# RX08b19.net
KiCad netlist of a schematic drawn in EAGLE
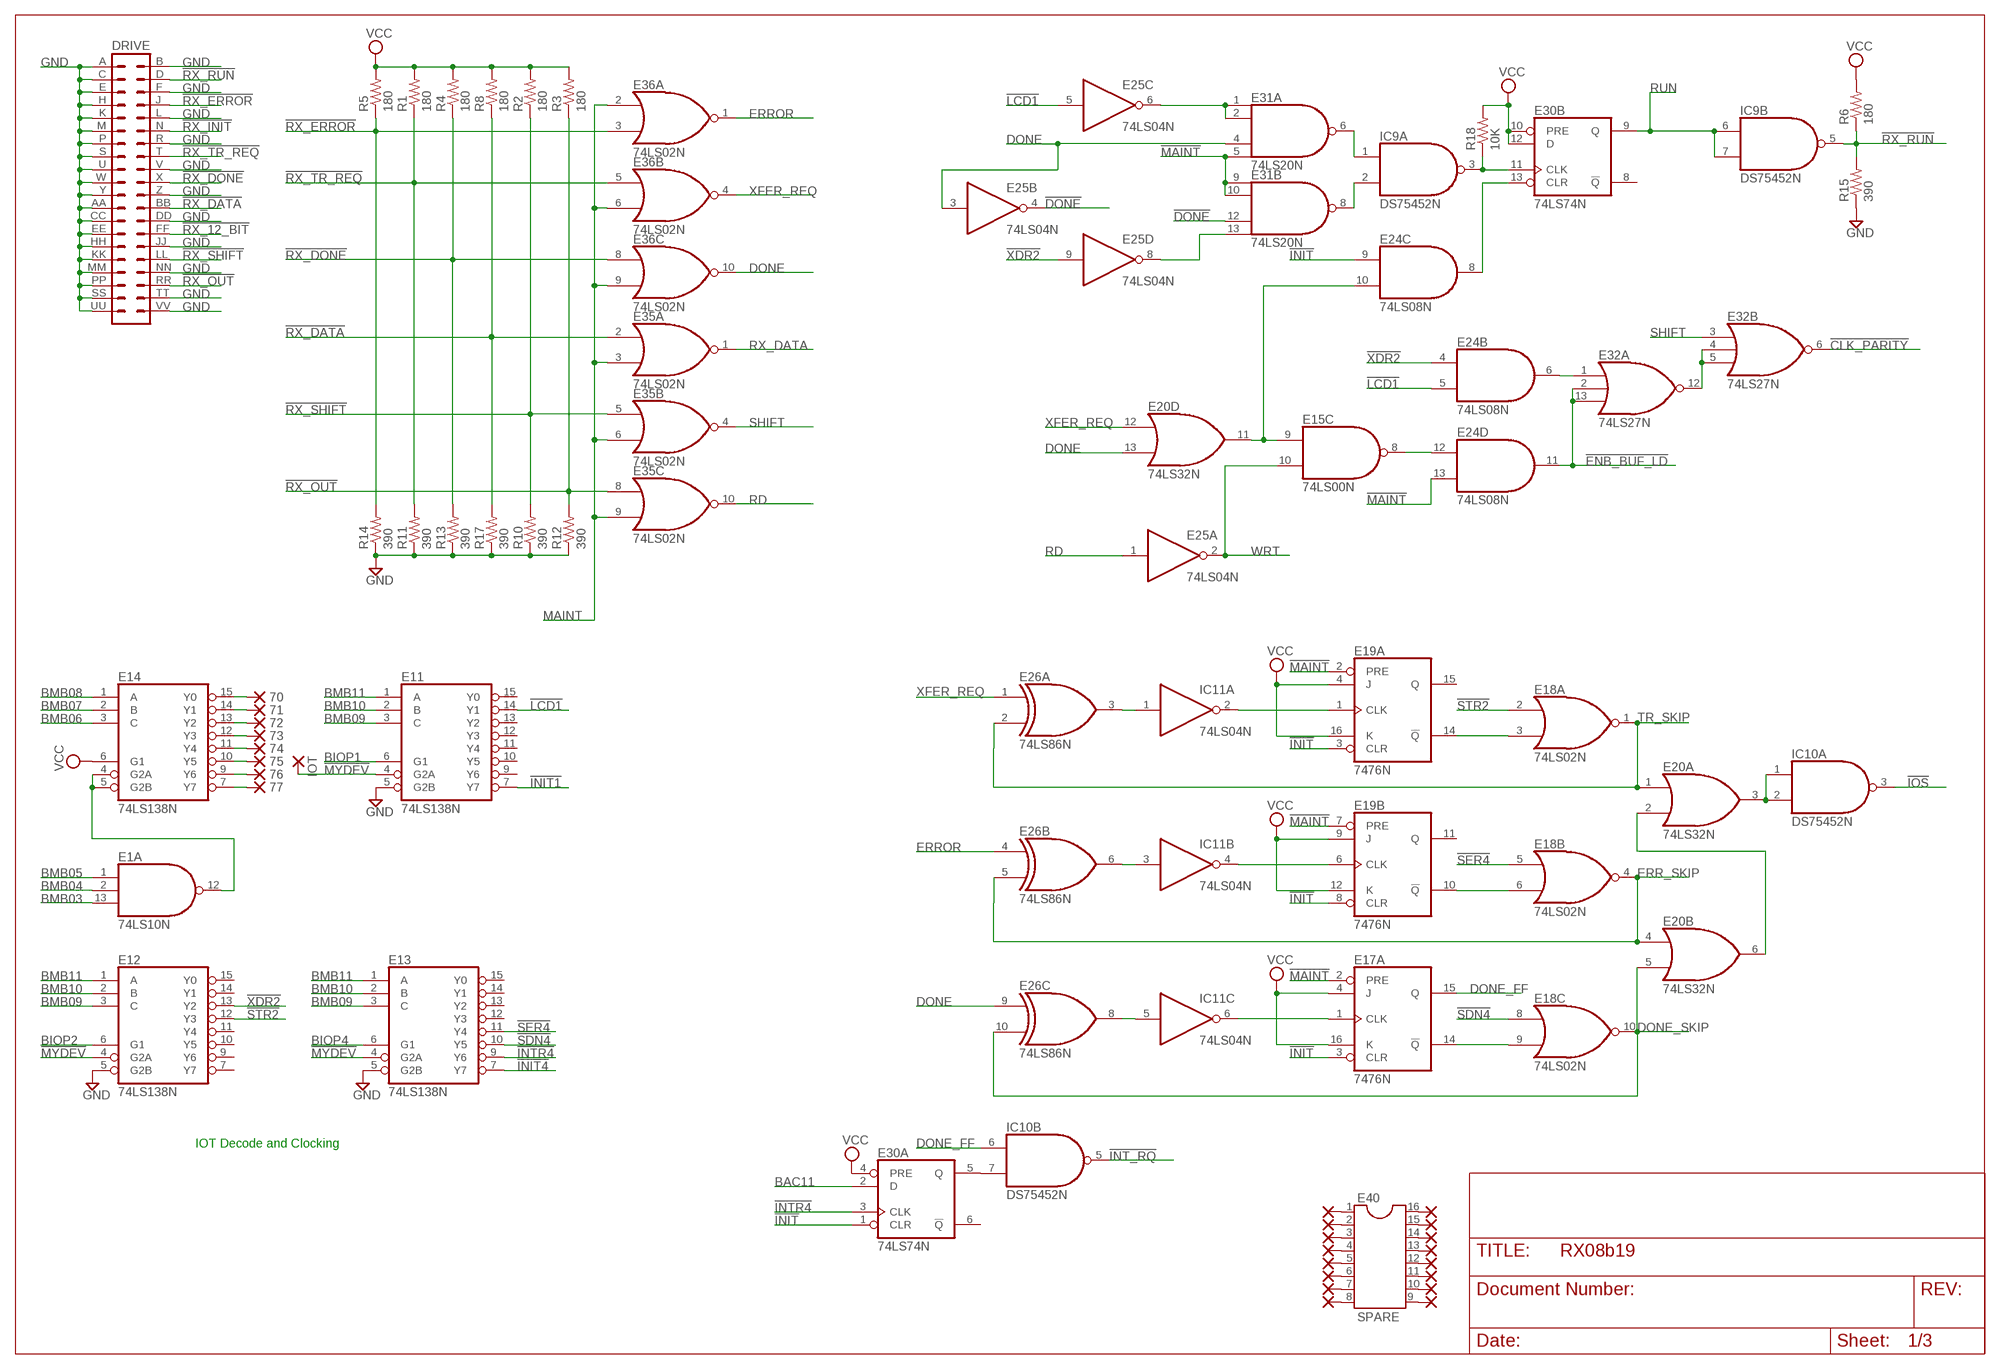
[diagram p0: schematic, sheet 1]
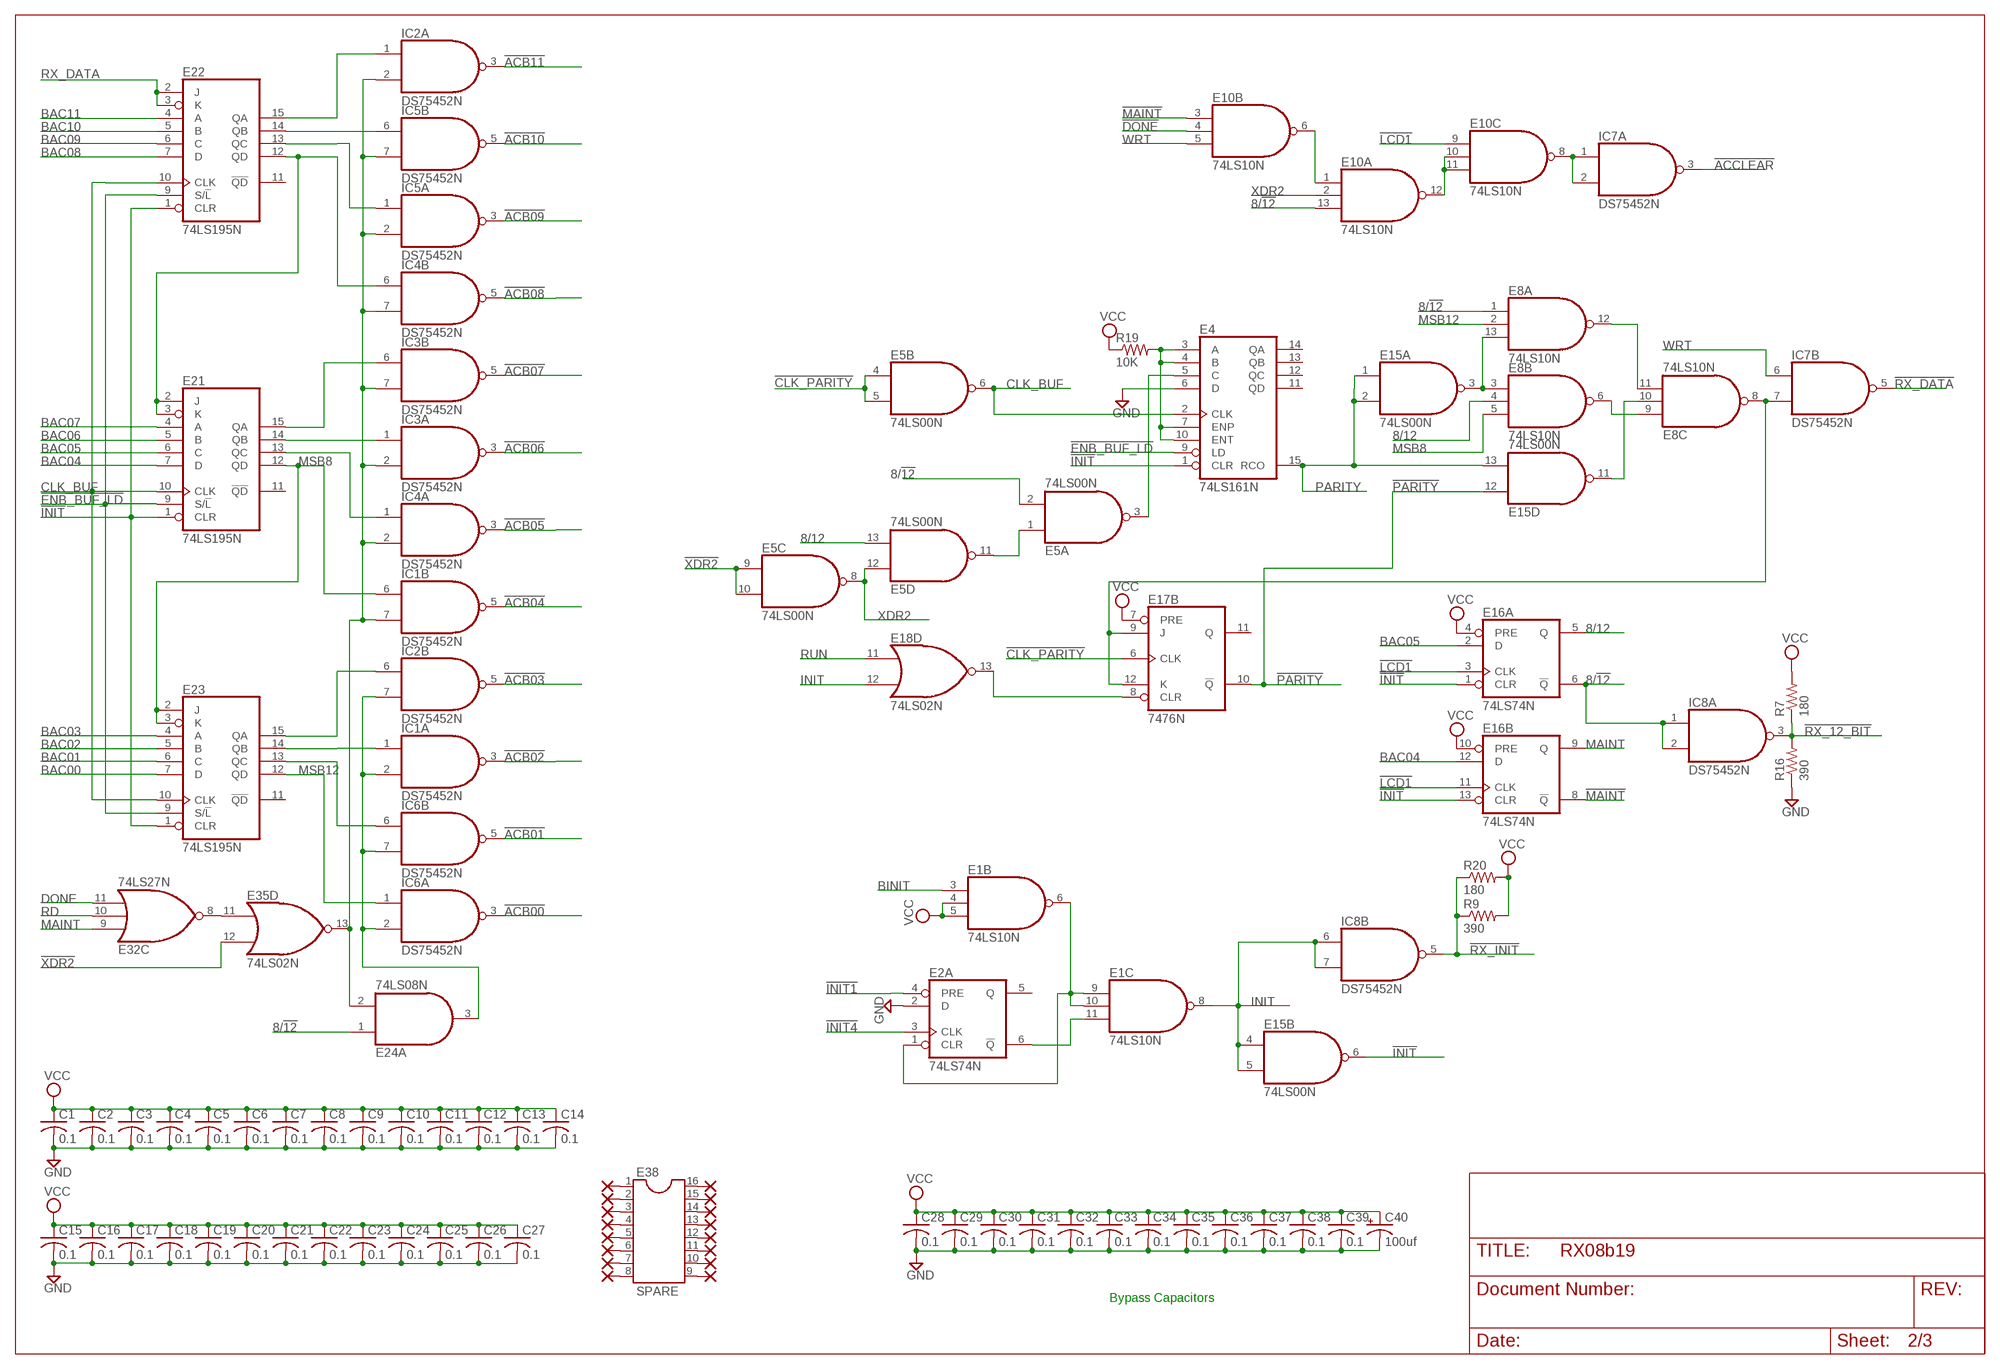
[diagram p1: schematic, sheet 2]
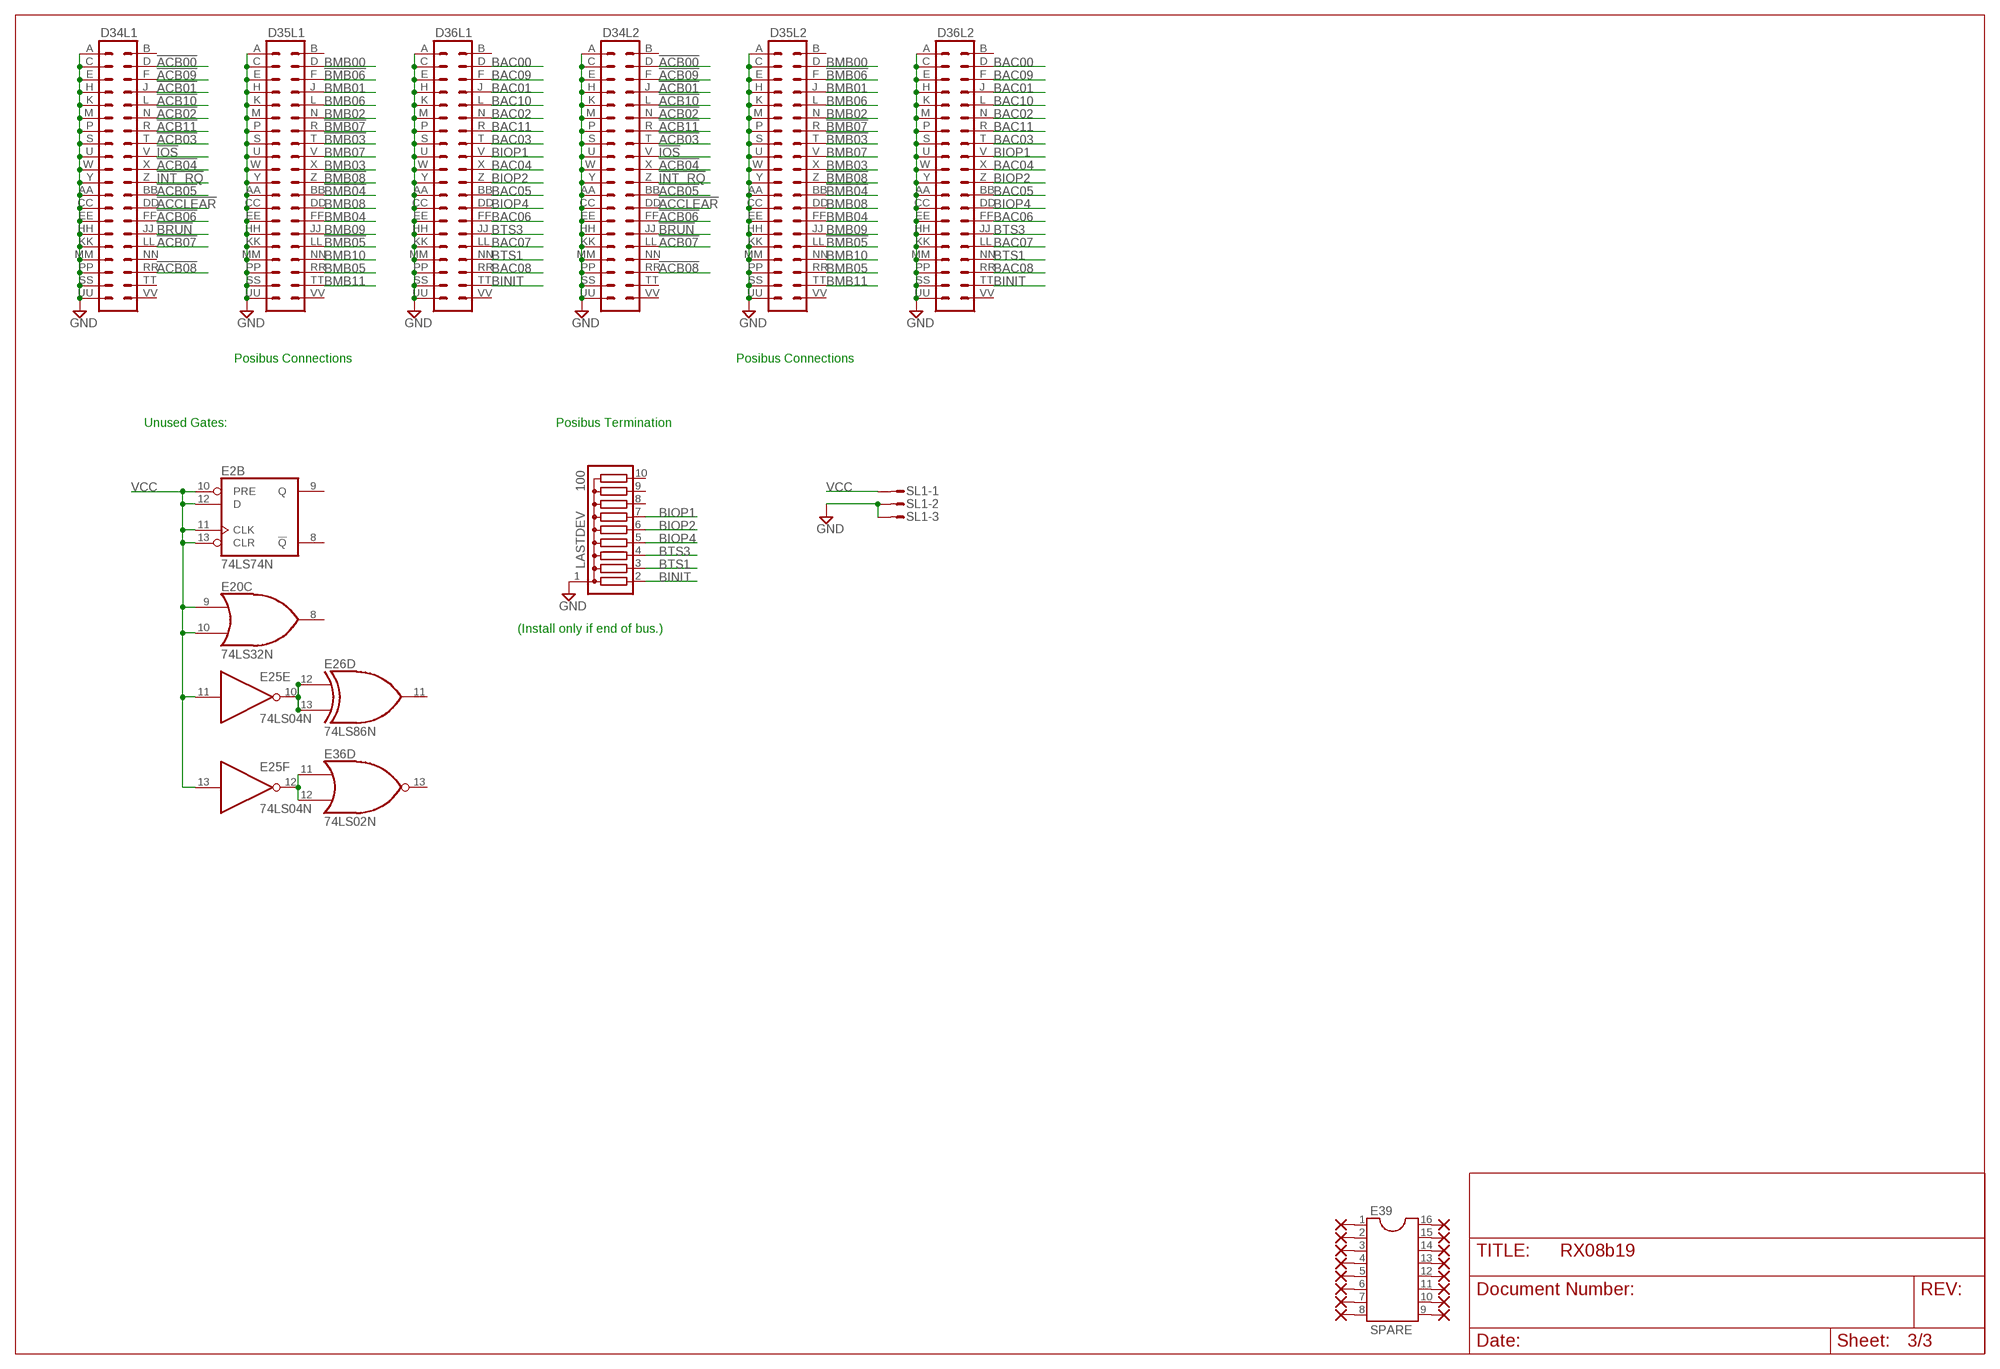
[diagram p2: schematic, sheet 3]

(export (version "E")
  (design (tool "Eeschema 10.0.6"))
  (components
    (comp (ref "C1")
      (value "0.1")
      (footprint "eagle-import:C050-025X075")
      (libsource (lib "eagle-import") (part "C-US050-025X075"))
    )
    (comp (ref "C2")
      (value "0.1")
      (footprint "eagle-import:C050-025X075")
      (libsource (lib "eagle-import") (part "C-US050-025X075"))
    )
    (comp (ref "C3")
      (value "0.1")
      (footprint "eagle-import:C050-025X075")
      (libsource (lib "eagle-import") (part "C-US050-025X075"))
    )
    (comp (ref "C4")
      (value "0.1")
      (footprint "eagle-import:C050-025X075")
      (libsource (lib "eagle-import") (part "C-US050-025X075"))
    )
    (comp (ref "C5")
      (value "0.1")
      (footprint "eagle-import:C050-025X075")
      (libsource (lib "eagle-import") (part "C-US050-025X075"))
    )
    (comp (ref "C6")
      (value "0.1")
      (footprint "eagle-import:C050-025X075")
      (libsource (lib "eagle-import") (part "C-US050-025X075"))
    )
    (comp (ref "C7")
      (value "0.1")
      (footprint "eagle-import:C050-025X075")
      (libsource (lib "eagle-import") (part "C-US050-025X075"))
    )
    (comp (ref "C8")
      (value "0.1")
      (footprint "eagle-import:C050-025X075")
      (libsource (lib "eagle-import") (part "C-US050-025X075"))
    )
    (comp (ref "C9")
      (value "0.1")
      (footprint "eagle-import:C050-025X075")
      (libsource (lib "eagle-import") (part "C-US050-025X075"))
    )
    (comp (ref "C10")
      (value "0.1")
      (footprint "eagle-import:C050-025X075")
      (libsource (lib "eagle-import") (part "C-US050-025X075"))
    )
    (comp (ref "C11")
      (value "0.1")
      (footprint "eagle-import:C050-025X075")
      (libsource (lib "eagle-import") (part "C-US050-025X075"))
    )
    (comp (ref "C12")
      (value "0.1")
      (footprint "eagle-import:C050-025X075")
      (libsource (lib "eagle-import") (part "C-US050-025X075"))
    )
    (comp (ref "C13")
      (value "0.1")
      (footprint "eagle-import:C050-025X075")
      (libsource (lib "eagle-import") (part "C-US050-025X075"))
    )
    (comp (ref "C14")
      (value "0.1")
      (footprint "eagle-import:C050-025X075")
      (libsource (lib "eagle-import") (part "C-US050-025X075"))
    )
    (comp (ref "C15")
      (value "0.1")
      (footprint "eagle-import:C050-025X075")
      (libsource (lib "eagle-import") (part "C-US050-025X075"))
    )
    (comp (ref "C16")
      (value "0.1")
      (footprint "eagle-import:C050-025X075")
      (libsource (lib "eagle-import") (part "C-US050-025X075"))
    )
    (comp (ref "C17")
      (value "0.1")
      (footprint "eagle-import:C050-025X075")
      (libsource (lib "eagle-import") (part "C-US050-025X075"))
    )
    (comp (ref "C18")
      (value "0.1")
      (footprint "eagle-import:C050-025X075")
      (libsource (lib "eagle-import") (part "C-US050-025X075"))
    )
    (comp (ref "C19")
      (value "0.1")
      (footprint "eagle-import:C050-025X075")
      (libsource (lib "eagle-import") (part "C-US050-025X075"))
    )
    (comp (ref "C20")
      (value "0.1")
      (footprint "eagle-import:C050-025X075")
      (libsource (lib "eagle-import") (part "C-US050-025X075"))
    )
    (comp (ref "C21")
      (value "0.1")
      (footprint "eagle-import:C050-025X075")
      (libsource (lib "eagle-import") (part "C-US050-025X075"))
    )
    (comp (ref "C22")
      (value "0.1")
      (footprint "eagle-import:C050-025X075")
      (libsource (lib "eagle-import") (part "C-US050-025X075"))
    )
    (comp (ref "C23")
      (value "0.1")
      (footprint "eagle-import:C050-025X075")
      (libsource (lib "eagle-import") (part "C-US050-025X075"))
    )
    (comp (ref "C24")
      (value "0.1")
      (footprint "eagle-import:C050-025X075")
      (libsource (lib "eagle-import") (part "C-US050-025X075"))
    )
    (comp (ref "C25")
      (value "0.1")
      (footprint "eagle-import:C050-025X075")
      (libsource (lib "eagle-import") (part "C-US050-025X075"))
    )
    (comp (ref "C26")
      (value "0.1")
      (footprint "eagle-import:C050-025X075")
      (libsource (lib "eagle-import") (part "C-US050-025X075"))
    )
    (comp (ref "C27")
      (value "0.1")
      (footprint "eagle-import:C050-025X075")
      (libsource (lib "eagle-import") (part "C-US050-025X075"))
    )
    (comp (ref "C28")
      (value "0.1")
      (footprint "eagle-import:C050-025X075")
      (libsource (lib "eagle-import") (part "C-US050-025X075"))
    )
    (comp (ref "C29")
      (value "0.1")
      (footprint "eagle-import:C050-025X075")
      (libsource (lib "eagle-import") (part "C-US050-025X075"))
    )
    (comp (ref "C30")
      (value "0.1")
      (footprint "eagle-import:C050-025X075")
      (libsource (lib "eagle-import") (part "C-US050-025X075"))
    )
    (comp (ref "C31")
      (value "0.1")
      (footprint "eagle-import:C050-025X075")
      (libsource (lib "eagle-import") (part "C-US050-025X075"))
    )
    (comp (ref "C32")
      (value "0.1")
      (footprint "eagle-import:C050-025X075")
      (libsource (lib "eagle-import") (part "C-US050-025X075"))
    )
    (comp (ref "C33")
      (value "0.1")
      (footprint "eagle-import:C050-025X075")
      (libsource (lib "eagle-import") (part "C-US050-025X075"))
    )
    (comp (ref "C34")
      (value "0.1")
      (footprint "eagle-import:C050-025X075")
      (libsource (lib "eagle-import") (part "C-US050-025X075"))
    )
    (comp (ref "C35")
      (value "0.1")
      (footprint "eagle-import:C050-025X075")
      (libsource (lib "eagle-import") (part "C-US050-025X075"))
    )
    (comp (ref "C36")
      (value "0.1")
      (footprint "eagle-import:C050-025X075")
      (libsource (lib "eagle-import") (part "C-US050-025X075"))
    )
    (comp (ref "C37")
      (value "0.1")
      (footprint "eagle-import:C050-025X075")
      (libsource (lib "eagle-import") (part "C-US050-025X075"))
    )
    (comp (ref "C38")
      (value "0.1")
      (footprint "eagle-import:C050-025X075")
      (libsource (lib "eagle-import") (part "C-US050-025X075"))
    )
    (comp (ref "C39")
      (value "0.1")
      (footprint "eagle-import:C050-025X075")
      (libsource (lib "eagle-import") (part "C-US050-025X075"))
    )
    (comp (ref "C40")
      (value "100uf")
      (footprint "eagle-import:E22-9")
      (libsource (lib "eagle-import") (part "CPOL-USE22-9AXIAL"))
    )
    (comp (ref "E1")
      (value "74LS10N")
      (footprint "eagle-import:DIL14")
      (libsource (lib "eagle-import") (part "7410NLS"))
    )
    (comp (ref "E2")
      (value "74LS74N")
      (footprint "eagle-import:DIL14")
      (libsource (lib "eagle-import") (part "7474NLS"))
    )
    (comp (ref "E4")
      (value "74LS161N")
      (footprint "eagle-import:DIL16")
      (libsource (lib "eagle-import") (part "74161NLS"))
    )
    (comp (ref "E5")
      (value "74LS00N")
      (footprint "eagle-import:DIL14")
      (libsource (lib "eagle-import") (part "7400NLS"))
    )
    (comp (ref "E8")
      (value "74LS10N")
      (footprint "eagle-import:DIL14")
      (libsource (lib "eagle-import") (part "7410NLS"))
    )
    (comp (ref "E10")
      (value "74LS10N")
      (footprint "eagle-import:DIL14")
      (libsource (lib "eagle-import") (part "7410NLS"))
    )
    (comp (ref "E15")
      (value "74LS00N")
      (footprint "eagle-import:DIL14")
      (libsource (lib "eagle-import") (part "7400NLS"))
    )
    (comp (ref "E16")
      (value "74LS74N")
      (footprint "eagle-import:DIL14")
      (libsource (lib "eagle-import") (part "7474NLS"))
    )
    (comp (ref "E17")
      (value "7476N")
      (footprint "eagle-import:DIL16")
      (libsource (lib "eagle-import") (part "7476N"))
    )
    (comp (ref "E18")
      (value "74LS02N")
      (footprint "eagle-import:DIL14")
      (libsource (lib "eagle-import") (part "7402NLS"))
    )
    (comp (ref "E21")
      (value "74LS195N")
      (footprint "eagle-import:DIL16")
      (libsource (lib "eagle-import") (part "74195NLS"))
    )
    (comp (ref "E22")
      (value "74LS195N")
      (footprint "eagle-import:DIL16")
      (libsource (lib "eagle-import") (part "74195NLS"))
    )
    (comp (ref "E23")
      (value "74LS195N")
      (footprint "eagle-import:DIL16")
      (libsource (lib "eagle-import") (part "74195NLS"))
    )
    (comp (ref "E24")
      (value "74LS08N")
      (footprint "eagle-import:DIL14")
      (libsource (lib "eagle-import") (part "7408NLS"))
    )
    (comp (ref "E32")
      (value "74LS27N")
      (footprint "eagle-import:DIL14")
      (libsource (lib "eagle-import") (part "7427NLS"))
    )
    (comp (ref "E35")
      (value "74LS02N")
      (footprint "eagle-import:DIL14")
      (libsource (lib "eagle-import") (part "7402NLS"))
    )
    (comp (ref "E38")
      (value "SPARE")
      (footprint "eagle-import:DIL16")
      (libsource (lib "eagle-import") (part "DIL16"))
    )
    (comp (ref "IC1")
      (value "DS75452N")
      (footprint "eagle-import:DIL08")
      (libsource (lib "eagle-import") (part "DS75452N"))
    )
    (comp (ref "IC2")
      (value "DS75452N")
      (footprint "eagle-import:DIL08")
      (libsource (lib "eagle-import") (part "DS75452N"))
    )
    (comp (ref "IC3")
      (value "DS75452N")
      (footprint "eagle-import:DIL08")
      (libsource (lib "eagle-import") (part "DS75452N"))
    )
    (comp (ref "IC4")
      (value "DS75452N")
      (footprint "eagle-import:DIL08")
      (libsource (lib "eagle-import") (part "DS75452N"))
    )
    (comp (ref "IC5")
      (value "DS75452N")
      (footprint "eagle-import:DIL08")
      (libsource (lib "eagle-import") (part "DS75452N"))
    )
    (comp (ref "IC6")
      (value "DS75452N")
      (footprint "eagle-import:DIL08")
      (libsource (lib "eagle-import") (part "DS75452N"))
    )
    (comp (ref "IC7")
      (value "DS75452N")
      (footprint "eagle-import:DIL08")
      (libsource (lib "eagle-import") (part "DS75452N"))
    )
    (comp (ref "IC8")
      (value "DS75452N")
      (footprint "eagle-import:DIL08")
      (libsource (lib "eagle-import") (part "DS75452N"))
    )
    (comp (ref "PAD10")
      (value "1,6/0,8")
      (footprint "eagle-import:1,6_0,8")
      (libsource (lib "eagle-import") (part "1,6/0,8"))
    )
    (comp (ref "PAD11")
      (value "1,6/0,8")
      (footprint "eagle-import:1,6_0,8")
      (libsource (lib "eagle-import") (part "1,6/0,8"))
    )
    (comp (ref "PAD12")
      (value "1,6/0,8")
      (footprint "eagle-import:1,6_0,8")
      (libsource (lib "eagle-import") (part "1,6/0,8"))
    )
    (comp (ref "PAD13")
      (value "1,6/0,8")
      (footprint "eagle-import:1,6_0,8")
      (libsource (lib "eagle-import") (part "1,6/0,8"))
    )
    (comp (ref "PAD14")
      (value "1,6/0,8")
      (footprint "eagle-import:1,6_0,8")
      (libsource (lib "eagle-import") (part "1,6/0,8"))
    )
    (comp (ref "PAD15")
      (value "1,6/0,8")
      (footprint "eagle-import:1,6_0,8")
      (libsource (lib "eagle-import") (part "1,6/0,8"))
    )
    (comp (ref "PAD16")
      (value "1,6/0,8")
      (footprint "eagle-import:1,6_0,8")
      (libsource (lib "eagle-import") (part "1,6/0,8"))
    )
    (comp (ref "PAD17")
      (value "1,6/0,8")
      (footprint "eagle-import:1,6_0,8")
      (libsource (lib "eagle-import") (part "1,6/0,8"))
    )
    (comp (ref "PAD20")
      (value "1,6/0,8")
      (footprint "eagle-import:1,6_0,8")
      (libsource (lib "eagle-import") (part "1,6/0,8"))
    )
    (comp (ref "PAD21")
      (value "1,6/0,8")
      (footprint "eagle-import:1,6_0,8")
      (libsource (lib "eagle-import") (part "1,6/0,8"))
    )
    (comp (ref "PAD22")
      (value "1,6/0,8")
      (footprint "eagle-import:1,6_0,8")
      (libsource (lib "eagle-import") (part "1,6/0,8"))
    )
    (comp (ref "PAD23")
      (value "1,6/0,8")
      (footprint "eagle-import:1,6_0,8")
      (libsource (lib "eagle-import") (part "1,6/0,8"))
    )
    (comp (ref "PAD24")
      (value "1,6/0,8")
      (footprint "eagle-import:1,6_0,8")
      (libsource (lib "eagle-import") (part "1,6/0,8"))
    )
    (comp (ref "PAD25")
      (value "1,6/0,8")
      (footprint "eagle-import:1,6_0,8")
      (libsource (lib "eagle-import") (part "1,6/0,8"))
    )
    (comp (ref "PAD26")
      (value "1,6/0,8")
      (footprint "eagle-import:1,6_0,8")
      (libsource (lib "eagle-import") (part "1,6/0,8"))
    )
    (comp (ref "PAD27")
      (value "1,6/0,8")
      (footprint "eagle-import:1,6_0,8")
      (libsource (lib "eagle-import") (part "1,6/0,8"))
    )
    (comp (ref "R7")
      (value "180")
      (footprint "eagle-import:0207_10")
      (libsource (lib "eagle-import") (part "R-US_0207/10"))
    )
    (comp (ref "R9")
      (value "390")
      (footprint "eagle-import:0207_10")
      (libsource (lib "eagle-import") (part "R-US_0207/10"))
    )
    (comp (ref "R16")
      (value "390")
      (footprint "eagle-import:0207_10")
      (libsource (lib "eagle-import") (part "R-US_0207/10"))
    )
    (comp (ref "R19")
      (value "10K")
      (footprint "eagle-import:0207_10")
      (libsource (lib "eagle-import") (part "R-US_0207/10"))
    )
    (comp (ref "R20")
      (value "180")
      (footprint "eagle-import:0207_10")
      (libsource (lib "eagle-import") (part "R-US_0207/10"))
    )
    (comp (ref "D34L1")
      (value "DEC40PINV")
      (footprint "eagle-import:DEC40PINV")
      (libsource (lib "eagle-import") (part "DEC40PINV"))
    )
    (comp (ref "D34L2")
      (value "DEC40PINV")
      (footprint "eagle-import:DEC40PINV")
      (libsource (lib "eagle-import") (part "DEC40PINV"))
    )
    (comp (ref "D35L1")
      (value "DEC40PINV")
      (footprint "eagle-import:DEC40PINV")
      (libsource (lib "eagle-import") (part "DEC40PINV"))
    )
    (comp (ref "D35L2")
      (value "DEC40PINV")
      (footprint "eagle-import:DEC40PINV")
      (libsource (lib "eagle-import") (part "DEC40PINV"))
    )
    (comp (ref "D36L1")
      (value "DEC40PINV")
      (footprint "eagle-import:DEC40PINV")
      (libsource (lib "eagle-import") (part "DEC40PINV"))
    )
    (comp (ref "D36L2")
      (value "DEC40PINV")
      (footprint "eagle-import:DEC40PINV")
      (libsource (lib "eagle-import") (part "DEC40PINV"))
    )
    (comp (ref "E20")
      (value "74LS32N")
      (footprint "eagle-import:DIL14")
      (libsource (lib "eagle-import") (part "7432NLS"))
    )
    (comp (ref "E25")
      (value "74LS04N")
      (footprint "eagle-import:DIL14")
      (libsource (lib "eagle-import") (part "7404NLS"))
    )
    (comp (ref "E26")
      (value "74LS86N")
      (footprint "eagle-import:DIL14")
      (libsource (lib "eagle-import") (part "7486NLS"))
    )
    (comp (ref "E36")
      (value "74LS02N")
      (footprint "eagle-import:DIL14")
      (libsource (lib "eagle-import") (part "7402NLS"))
    )
    (comp (ref "E39")
      (value "SPARE")
      (footprint "eagle-import:DIL16")
      (libsource (lib "eagle-import") (part "DIL16"))
    )
    (comp (ref "LASTDEV")
      (value "100")
      (footprint "eagle-import:SIL10")
      (libsource (lib "eagle-import") (part "G09R"))
    )
    (comp (ref "PAD42")
      (value "1,6/0,8")
      (footprint "eagle-import:1,6_0,8")
      (libsource (lib "eagle-import") (part "1,6/0,8"))
    )
    (comp (ref "PAD43")
      (value "1,6/0,8")
      (footprint "eagle-import:1,6_0,8")
      (libsource (lib "eagle-import") (part "1,6/0,8"))
    )
    (comp (ref "PAD44")
      (value "1,6/0,8")
      (footprint "eagle-import:1,6_0,8")
      (libsource (lib "eagle-import") (part "1,6/0,8"))
    )
    (comp (ref "PAD45")
      (value "1,6/0,8")
      (footprint "eagle-import:1,6_0,8")
      (libsource (lib "eagle-import") (part "1,6/0,8"))
    )
    (comp (ref "PAD46")
      (value "1,6/0,8")
      (footprint "eagle-import:1,6_0,8")
      (libsource (lib "eagle-import") (part "1,6/0,8"))
    )
    (comp (ref "PAD47")
      (value "1,6/0,8")
      (footprint "eagle-import:1,6_0,8")
      (libsource (lib "eagle-import") (part "1,6/0,8"))
    )
    (comp (ref "PAD48")
      (value "1,6/0,8")
      (footprint "eagle-import:1,6_0,8")
      (libsource (lib "eagle-import") (part "1,6/0,8"))
    )
    (comp (ref "PAD49")
      (value "1,6/0,8")
      (footprint "eagle-import:1,6_0,8")
      (libsource (lib "eagle-import") (part "1,6/0,8"))
    )
    (comp (ref "PAD50")
      (value "1,6/0,8")
      (footprint "eagle-import:1,6_0,8")
      (libsource (lib "eagle-import") (part "1,6/0,8"))
    )
    (comp (ref "PAD51")
      (value "1,6/0,8")
      (footprint "eagle-import:1,6_0,8")
      (libsource (lib "eagle-import") (part "1,6/0,8"))
    )
    (comp (ref "PAD52")
      (value "1,6/0,8")
      (footprint "eagle-import:1,6_0,8")
      (libsource (lib "eagle-import") (part "1,6/0,8"))
    )
    (comp (ref "PAD53")
      (value "1,6/0,8")
      (footprint "eagle-import:1,6_0,8")
      (libsource (lib "eagle-import") (part "1,6/0,8"))
    )
    (comp (ref "PAD54")
      (value "1,6/0,8")
      (footprint "eagle-import:1,6_0,8")
      (libsource (lib "eagle-import") (part "1,6/0,8"))
    )
    (comp (ref "PAD55")
      (value "1,6/0,8")
      (footprint "eagle-import:1,6_0,8")
      (libsource (lib "eagle-import") (part "1,6/0,8"))
    )
    (comp (ref "PAD56")
      (value "1,6/0,8")
      (footprint "eagle-import:1,6_0,8")
      (libsource (lib "eagle-import") (part "1,6/0,8"))
    )
    (comp (ref "PAD57")
      (value "1,6/0,8")
      (footprint "eagle-import:1,6_0,8")
      (libsource (lib "eagle-import") (part "1,6/0,8"))
    )
    (comp (ref "SL1")
      (value "MA04S")
      (footprint "eagle-import:04PA")
      (libsource (lib "eagle-import") (part "MA04S"))
    )
    (comp (ref "70")
      (value "1,6/0,8")
      (footprint "eagle-import:1,6_0,8")
      (libsource (lib "eagle-import") (part "1,6/0,8"))
    )
    (comp (ref "71")
      (value "1,6/0,8")
      (footprint "eagle-import:1,6_0,8")
      (libsource (lib "eagle-import") (part "1,6/0,8"))
    )
    (comp (ref "72")
      (value "1,6/0,8")
      (footprint "eagle-import:1,6_0,8")
      (libsource (lib "eagle-import") (part "1,6/0,8"))
    )
    (comp (ref "73")
      (value "1,6/0,8")
      (footprint "eagle-import:1,6_0,8")
      (libsource (lib "eagle-import") (part "1,6/0,8"))
    )
    (comp (ref "74")
      (value "1,6/0,8")
      (footprint "eagle-import:1,6_0,8")
      (libsource (lib "eagle-import") (part "1,6/0,8"))
    )
    (comp (ref "75")
      (value "1,6/0,8")
      (footprint "eagle-import:1,6_0,8")
      (libsource (lib "eagle-import") (part "1,6/0,8"))
    )
    (comp (ref "76")
      (value "1,6/0,8")
      (footprint "eagle-import:1,6_0,8")
      (libsource (lib "eagle-import") (part "1,6/0,8"))
    )
    (comp (ref "77")
      (value "1,6/0,8")
      (footprint "eagle-import:1,6_0,8")
      (libsource (lib "eagle-import") (part "1,6/0,8"))
    )
    (comp (ref "DRIVE")
      (value "DEC40PINV")
      (footprint "eagle-import:DEC40PINV")
      (libsource (lib "eagle-import") (part "DEC40PINV"))
    )
    (comp (ref "E11")
      (value "74LS138N")
      (footprint "eagle-import:DIL16")
      (libsource (lib "eagle-import") (part "74138NLS"))
    )
    (comp (ref "E12")
      (value "74LS138N")
      (footprint "eagle-import:DIL16")
      (libsource (lib "eagle-import") (part "74138NLS"))
    )
    (comp (ref "E13")
      (value "74LS138N")
      (footprint "eagle-import:DIL16")
      (libsource (lib "eagle-import") (part "74138NLS"))
    )
    (comp (ref "E14")
      (value "74LS138N")
      (footprint "eagle-import:DIL16")
      (libsource (lib "eagle-import") (part "74138NLS"))
    )
    (comp (ref "E19")
      (value "7476N")
      (footprint "eagle-import:DIL16")
      (libsource (lib "eagle-import") (part "7476N"))
    )
    (comp (ref "E30")
      (value "74LS74N")
      (footprint "eagle-import:DIL14")
      (libsource (lib "eagle-import") (part "7474NLS"))
    )
    (comp (ref "E31")
      (value "74LS20N")
      (footprint "eagle-import:DIL14")
      (libsource (lib "eagle-import") (part "7420NLS"))
    )
    (comp (ref "E40")
      (value "SPARE")
      (footprint "eagle-import:DIL16")
      (libsource (lib "eagle-import") (part "DIL16"))
    )
    (comp (ref "IC9")
      (value "DS75452N")
      (footprint "eagle-import:DIL08")
      (libsource (lib "eagle-import") (part "DS75452N"))
    )
    (comp (ref "IC10")
      (value "DS75452N")
      (footprint "eagle-import:DIL08")
      (libsource (lib "eagle-import") (part "DS75452N"))
    )
    (comp (ref "IC11")
      (value "74LS04N")
      (footprint "eagle-import:DIL14")
      (libsource (lib "eagle-import") (part "7404NLS"))
    )
    (comp (ref "IOT")
      (value "1,6/0,8")
      (footprint "eagle-import:1,6_0,8")
      (libsource (lib "eagle-import") (part "1,6/0,8"))
    )
    (comp (ref "PAD18")
      (value "1,6/0,8")
      (footprint "eagle-import:1,6_0,8")
      (libsource (lib "eagle-import") (part "1,6/0,8"))
    )
    (comp (ref "PAD19")
      (value "1,6/0,8")
      (footprint "eagle-import:1,6_0,8")
      (libsource (lib "eagle-import") (part "1,6/0,8"))
    )
    (comp (ref "PAD28")
      (value "1,6/0,8")
      (footprint "eagle-import:1,6_0,8")
      (libsource (lib "eagle-import") (part "1,6/0,8"))
    )
    (comp (ref "PAD29")
      (value "1,6/0,8")
      (footprint "eagle-import:1,6_0,8")
      (libsource (lib "eagle-import") (part "1,6/0,8"))
    )
    (comp (ref "PAD30")
      (value "1,6/0,8")
      (footprint "eagle-import:1,6_0,8")
      (libsource (lib "eagle-import") (part "1,6/0,8"))
    )
    (comp (ref "PAD31")
      (value "1,6/0,8")
      (footprint "eagle-import:1,6_0,8")
      (libsource (lib "eagle-import") (part "1,6/0,8"))
    )
    (comp (ref "PAD32")
      (value "1,6/0,8")
      (footprint "eagle-import:1,6_0,8")
      (libsource (lib "eagle-import") (part "1,6/0,8"))
    )
    (comp (ref "PAD33")
      (value "1,6/0,8")
      (footprint "eagle-import:1,6_0,8")
      (libsource (lib "eagle-import") (part "1,6/0,8"))
    )
    (comp (ref "PAD34")
      (value "1,6/0,8")
      (footprint "eagle-import:1,6_0,8")
      (libsource (lib "eagle-import") (part "1,6/0,8"))
    )
    (comp (ref "PAD35")
      (value "1,6/0,8")
      (footprint "eagle-import:1,6_0,8")
      (libsource (lib "eagle-import") (part "1,6/0,8"))
    )
    (comp (ref "PAD36")
      (value "1,6/0,8")
      (footprint "eagle-import:1,6_0,8")
      (libsource (lib "eagle-import") (part "1,6/0,8"))
    )
    (comp (ref "PAD37")
      (value "1,6/0,8")
      (footprint "eagle-import:1,6_0,8")
      (libsource (lib "eagle-import") (part "1,6/0,8"))
    )
    (comp (ref "PAD38")
      (value "1,6/0,8")
      (footprint "eagle-import:1,6_0,8")
      (libsource (lib "eagle-import") (part "1,6/0,8"))
    )
    (comp (ref "PAD39")
      (value "1,6/0,8")
      (footprint "eagle-import:1,6_0,8")
      (libsource (lib "eagle-import") (part "1,6/0,8"))
    )
    (comp (ref "PAD40")
      (value "1,6/0,8")
      (footprint "eagle-import:1,6_0,8")
      (libsource (lib "eagle-import") (part "1,6/0,8"))
    )
    (comp (ref "PAD41")
      (value "1,6/0,8")
      (footprint "eagle-import:1,6_0,8")
      (libsource (lib "eagle-import") (part "1,6/0,8"))
    )
    (comp (ref "R1")
      (value "180")
      (footprint "eagle-import:0207_10")
      (libsource (lib "eagle-import") (part "R-US_0207/10"))
    )
    (comp (ref "R2")
      (value "180")
      (footprint "eagle-import:0207_10")
      (libsource (lib "eagle-import") (part "R-US_0207/10"))
    )
    (comp (ref "R3")
      (value "180")
      (footprint "eagle-import:0207_10")
      (libsource (lib "eagle-import") (part "R-US_0207/10"))
    )
    (comp (ref "R4")
      (value "180")
      (footprint "eagle-import:0207_10")
      (libsource (lib "eagle-import") (part "R-US_0207/10"))
    )
    (comp (ref "R5")
      (value "180")
      (footprint "eagle-import:0207_10")
      (libsource (lib "eagle-import") (part "R-US_0207/10"))
    )
    (comp (ref "R6")
      (value "180")
      (footprint "eagle-import:0207_10")
      (libsource (lib "eagle-import") (part "R-US_0207/10"))
    )
    (comp (ref "R8")
      (value "180")
      (footprint "eagle-import:0207_10")
      (libsource (lib "eagle-import") (part "R-US_0207/10"))
    )
    (comp (ref "R10")
      (value "390")
      (footprint "eagle-import:0207_10")
      (libsource (lib "eagle-import") (part "R-US_0207/10"))
    )
    (comp (ref "R11")
      (value "390")
      (footprint "eagle-import:0207_10")
      (libsource (lib "eagle-import") (part "R-US_0207/10"))
    )
    (comp (ref "R12")
      (value "390")
      (footprint "eagle-import:0207_10")
      (libsource (lib "eagle-import") (part "R-US_0207/10"))
    )
    (comp (ref "R13")
      (value "390")
      (footprint "eagle-import:0207_10")
      (libsource (lib "eagle-import") (part "R-US_0207/10"))
    )
    (comp (ref "R14")
      (value "390")
      (footprint "eagle-import:0207_10")
      (libsource (lib "eagle-import") (part "R-US_0207/10"))
    )
    (comp (ref "R15")
      (value "390")
      (footprint "eagle-import:0207_10")
      (libsource (lib "eagle-import") (part "R-US_0207/10"))
    )
    (comp (ref "R17")
      (value "390")
      (footprint "eagle-import:0207_10")
      (libsource (lib "eagle-import") (part "R-US_0207/10"))
    )
    (comp (ref "R18")
      (value "10K")
      (footprint "eagle-import:0207_10")
      (libsource (lib "eagle-import") (part "R-US_0207/10"))
    )
  )
  (nets
    (net (code "1") (name "8{slash}12") (class "Default")
      (node (ref "E16") (pin "5") (pinfunction "Q_5") (pintype "output"))
      (node (ref "E5") (pin "13") (pinfunction "I1_13") (pintype "input"))
      (node (ref "E8") (pin "4") (pinfunction "I1_4") (pintype "input"))
    )
    (net (code "2") (name "8{slash}~{12}") (class "Default")
      (node (ref "E10") (pin "13") (pinfunction "I2_13") (pintype "input"))
      (node (ref "E16") (pin "6") (pinfunction "~{Q}_6") (pintype "output"))
      (node (ref "E24") (pin "1") (pinfunction "I0_1") (pintype "input"))
      (node (ref "E5") (pin "2") (pinfunction "I1_2") (pintype "input"))
      (node (ref "E8") (pin "1") (pinfunction "I0_1") (pintype "input"))
      (node (ref "IC8") (pin "1") (pinfunction "I0_1") (pintype "input"))
      (node (ref "IC8") (pin "2") (pinfunction "I1_2") (pintype "input"))
    )
    (net (code "3") (name "BAC00") (class "Default")
      (node (ref "D36L1") (pin "D") (pinfunction "4_D") (pintype "bidirectional"))
      (node (ref "D36L2") (pin "D") (pinfunction "4_D") (pintype "bidirectional"))
      (node (ref "E23") (pin "7") (pinfunction "D_7") (pintype "input"))
    )
    (net (code "4") (name "BAC01") (class "Default")
      (node (ref "D36L1") (pin "J") (pinfunction "8_J") (pintype "bidirectional"))
      (node (ref "D36L2") (pin "J") (pinfunction "8_J") (pintype "bidirectional"))
      (node (ref "E23") (pin "6") (pinfunction "C_6") (pintype "input"))
    )
    (net (code "5") (name "BAC02") (class "Default")
      (node (ref "D36L1") (pin "N") (pinfunction "12_N") (pintype "bidirectional"))
      (node (ref "D36L2") (pin "N") (pinfunction "12_N") (pintype "bidirectional"))
      (node (ref "E23") (pin "5") (pinfunction "B_5") (pintype "input"))
    )
    (net (code "6") (name "BAC03") (class "Default")
      (node (ref "D36L1") (pin "T") (pinfunction "16_T") (pintype "bidirectional"))
      (node (ref "D36L2") (pin "T") (pinfunction "16_T") (pintype "bidirectional"))
      (node (ref "E23") (pin "4") (pinfunction "A_4") (pintype "input"))
    )
    (net (code "7") (name "BAC04") (class "Default")
      (node (ref "D36L1") (pin "X") (pinfunction "20_X") (pintype "bidirectional"))
      (node (ref "D36L2") (pin "X") (pinfunction "20_X") (pintype "bidirectional"))
      (node (ref "E16") (pin "12") (pinfunction "D_12") (pintype "input"))
      (node (ref "E21") (pin "7") (pinfunction "D_7") (pintype "input"))
    )
    (net (code "8") (name "BAC05") (class "Default")
      (node (ref "D36L1") (pin "BB") (pinfunction "24_BB") (pintype "bidirectional"))
      (node (ref "D36L2") (pin "BB") (pinfunction "24_BB") (pintype "bidirectional"))
      (node (ref "E16") (pin "2") (pinfunction "D_2") (pintype "input"))
      (node (ref "E21") (pin "6") (pinfunction "C_6") (pintype "input"))
    )
    (net (code "9") (name "BAC06") (class "Default")
      (node (ref "D36L1") (pin "FF") (pinfunction "28_FF") (pintype "bidirectional"))
      (node (ref "D36L2") (pin "FF") (pinfunction "28_FF") (pintype "bidirectional"))
      (node (ref "E21") (pin "5") (pinfunction "B_5") (pintype "input"))
    )
    (net (code "10") (name "BAC07") (class "Default")
      (node (ref "D36L1") (pin "LL") (pinfunction "32_LL") (pintype "bidirectional"))
      (node (ref "D36L2") (pin "LL") (pinfunction "32_LL") (pintype "bidirectional"))
      (node (ref "E21") (pin "4") (pinfunction "A_4") (pintype "input"))
    )
    (net (code "11") (name "BAC08") (class "Default")
      (node (ref "D36L1") (pin "RR") (pinfunction "36_RR") (pintype "bidirectional"))
      (node (ref "D36L2") (pin "RR") (pinfunction "36_RR") (pintype "bidirectional"))
      (node (ref "E22") (pin "7") (pinfunction "D_7") (pintype "input"))
    )
    (net (code "12") (name "BAC09") (class "Default")
      (node (ref "D36L1") (pin "F") (pinfunction "6_F") (pintype "bidirectional"))
      (node (ref "D36L2") (pin "F") (pinfunction "6_F") (pintype "bidirectional"))
      (node (ref "E22") (pin "6") (pinfunction "C_6") (pintype "input"))
    )
    (net (code "13") (name "BAC10") (class "Default")
      (node (ref "D36L1") (pin "L") (pinfunction "10_L") (pintype "bidirectional"))
      (node (ref "D36L2") (pin "L") (pinfunction "10_L") (pintype "bidirectional"))
      (node (ref "E22") (pin "5") (pinfunction "B_5") (pintype "input"))
    )
    (net (code "14") (name "BAC11") (class "Default")
      (node (ref "D36L1") (pin "R") (pinfunction "14_R") (pintype "bidirectional"))
      (node (ref "D36L2") (pin "R") (pinfunction "14_R") (pintype "bidirectional"))
      (node (ref "E22") (pin "4") (pinfunction "A_4") (pintype "input"))
      (node (ref "E30") (pin "2") (pinfunction "D_2") (pintype "input"))
    )
    (net (code "15") (name "BINIT") (class "Default")
      (node (ref "D36L1") (pin "TT") (pinfunction "38_TT") (pintype "bidirectional"))
      (node (ref "D36L2") (pin "TT") (pinfunction "38_TT") (pintype "bidirectional"))
      (node (ref "E1") (pin "3") (pinfunction "I0_3") (pintype "input"))
      (node (ref "LASTDEV") (pin "2") (pinfunction "2_2") (pintype "passive"))
    )
    (net (code "16") (name "BIOP1") (class "Default")
      (node (ref "D36L1") (pin "V") (pinfunction "18_V") (pintype "bidirectional"))
      (node (ref "D36L2") (pin "V") (pinfunction "18_V") (pintype "bidirectional"))
      (node (ref "E11") (pin "6") (pinfunction "G1_6") (pintype "input"))
      (node (ref "LASTDEV") (pin "7") (pinfunction "7_7") (pintype "passive"))
    )
    (net (code "17") (name "BIOP2") (class "Default")
      (node (ref "D36L1") (pin "Z") (pinfunction "22_Z") (pintype "bidirectional"))
      (node (ref "D36L2") (pin "Z") (pinfunction "22_Z") (pintype "bidirectional"))
      (node (ref "E12") (pin "6") (pinfunction "G1_6") (pintype "input"))
      (node (ref "LASTDEV") (pin "6") (pinfunction "6_6") (pintype "passive"))
    )
    (net (code "18") (name "BIOP4") (class "Default")
      (node (ref "D36L1") (pin "DD") (pinfunction "26_DD") (pintype "bidirectional"))
      (node (ref "D36L2") (pin "DD") (pinfunction "26_DD") (pintype "bidirectional"))
      (node (ref "E13") (pin "6") (pinfunction "G1_6") (pintype "input"))
      (node (ref "LASTDEV") (pin "5") (pinfunction "5_5") (pintype "passive"))
    )
    (net (code "19") (name "BMB00") (class "Default")
      (node (ref "D35L1") (pin "D") (pinfunction "4_D") (pintype "bidirectional"))
      (node (ref "D35L2") (pin "D") (pinfunction "4_D") (pintype "bidirectional"))
    )
    (net (code "20") (name "BMB01") (class "Default")
      (node (ref "D35L1") (pin "J") (pinfunction "8_J") (pintype "bidirectional"))
      (node (ref "D35L2") (pin "J") (pinfunction "8_J") (pintype "bidirectional"))
    )
    (net (code "21") (name "BMB02") (class "Default")
      (node (ref "D35L1") (pin "N") (pinfunction "12_N") (pintype "bidirectional"))
      (node (ref "D35L2") (pin "N") (pinfunction "12_N") (pintype "bidirectional"))
    )
    (net (code "22") (name "BMB03") (class "Default")
      (node (ref "D35L1") (pin "X") (pinfunction "20_X") (pintype "bidirectional"))
      (node (ref "D35L2") (pin "X") (pinfunction "20_X") (pintype "bidirectional"))
      (node (ref "E1") (pin "13") (pinfunction "I2_13") (pintype "input"))
    )
    (net (code "23") (name "BMB04") (class "Default")
      (node (ref "D35L1") (pin "FF") (pinfunction "28_FF") (pintype "bidirectional"))
      (node (ref "D35L2") (pin "FF") (pinfunction "28_FF") (pintype "bidirectional"))
      (node (ref "E1") (pin "2") (pinfunction "I1_2") (pintype "input"))
    )
    (net (code "24") (name "BMB05") (class "Default")
      (node (ref "D35L1") (pin "RR") (pinfunction "36_RR") (pintype "bidirectional"))
      (node (ref "D35L2") (pin "RR") (pinfunction "36_RR") (pintype "bidirectional"))
      (node (ref "E1") (pin "1") (pinfunction "I0_1") (pintype "input"))
    )
    (net (code "25") (name "BMB06") (class "Default")
      (node (ref "D35L1") (pin "L") (pinfunction "10_L") (pintype "bidirectional"))
      (node (ref "D35L2") (pin "L") (pinfunction "10_L") (pintype "bidirectional"))
      (node (ref "E14") (pin "3") (pinfunction "C_3") (pintype "input"))
    )
    (net (code "26") (name "BMB07") (class "Default")
      (node (ref "D35L1") (pin "V") (pinfunction "18_V") (pintype "bidirectional"))
      (node (ref "D35L2") (pin "V") (pinfunction "18_V") (pintype "bidirectional"))
      (node (ref "E14") (pin "2") (pinfunction "B_2") (pintype "input"))
    )
    (net (code "27") (name "BMB08") (class "Default")
      (node (ref "D35L1") (pin "DD") (pinfunction "26_DD") (pintype "bidirectional"))
      (node (ref "D35L2") (pin "DD") (pinfunction "26_DD") (pintype "bidirectional"))
      (node (ref "E14") (pin "1") (pinfunction "A_1") (pintype "input"))
    )
    (net (code "28") (name "BMB09") (class "Default")
      (node (ref "D35L1") (pin "JJ") (pinfunction "30_JJ") (pintype "bidirectional"))
      (node (ref "D35L2") (pin "JJ") (pinfunction "30_JJ") (pintype "bidirectional"))
      (node (ref "E11") (pin "3") (pinfunction "C_3") (pintype "input"))
      (node (ref "E12") (pin "3") (pinfunction "C_3") (pintype "input"))
      (node (ref "E13") (pin "3") (pinfunction "C_3") (pintype "input"))
    )
    (net (code "29") (name "BMB10") (class "Default")
      (node (ref "D35L1") (pin "NN") (pinfunction "34_NN") (pintype "bidirectional"))
      (node (ref "D35L2") (pin "NN") (pinfunction "34_NN") (pintype "bidirectional"))
      (node (ref "E11") (pin "2") (pinfunction "B_2") (pintype "input"))
      (node (ref "E12") (pin "2") (pinfunction "B_2") (pintype "input"))
      (node (ref "E13") (pin "2") (pinfunction "B_2") (pintype "input"))
    )
    (net (code "30") (name "BMB11") (class "Default")
      (node (ref "D35L1") (pin "TT") (pinfunction "38_TT") (pintype "bidirectional"))
      (node (ref "D35L2") (pin "TT") (pinfunction "38_TT") (pintype "bidirectional"))
      (node (ref "E11") (pin "1") (pinfunction "A_1") (pintype "input"))
      (node (ref "E12") (pin "1") (pinfunction "A_1") (pintype "input"))
      (node (ref "E13") (pin "1") (pinfunction "A_1") (pintype "input"))
    )
    (net (code "31") (name "BTS1") (class "Default")
      (node (ref "D36L1") (pin "NN") (pinfunction "34_NN") (pintype "bidirectional"))
      (node (ref "D36L2") (pin "NN") (pinfunction "34_NN") (pintype "bidirectional"))
      (node (ref "LASTDEV") (pin "3") (pinfunction "3_3") (pintype "passive"))
    )
    (net (code "32") (name "BTS3") (class "Default")
      (node (ref "D36L1") (pin "JJ") (pinfunction "30_JJ") (pintype "bidirectional"))
      (node (ref "D36L2") (pin "JJ") (pinfunction "30_JJ") (pintype "bidirectional"))
      (node (ref "LASTDEV") (pin "4") (pinfunction "4_4") (pintype "passive"))
    )
    (net (code "33") (name "CLK_BUF") (class "Default")
      (node (ref "E21") (pin "10") (pinfunction "CLK_10") (pintype "input"))
      (node (ref "E22") (pin "10") (pinfunction "CLK_10") (pintype "input"))
      (node (ref "E23") (pin "10") (pinfunction "CLK_10") (pintype "input"))
      (node (ref "E4") (pin "2") (pinfunction "CLK_2") (pintype "input"))
      (node (ref "E5") (pin "6") (pinfunction "O_6") (pintype "output"))
    )
    (net (code "34") (name "DONE") (class "Default")
      (node (ref "E20") (pin "13") (pinfunction "I1_13") (pintype "input"))
      (node (ref "E25") (pin "3") (pinfunction "I_3") (pintype "input"))
      (node (ref "E26") (pin "9") (pinfunction "I0_9") (pintype "input"))
      (node (ref "E31") (pin "4") (pinfunction "I2_4") (pintype "input"))
      (node (ref "E32") (pin "11") (pinfunction "I2_11") (pintype "input"))
      (node (ref "E36") (pin "10") (pinfunction "O_10") (pintype "output"))
    )
    (net (code "35") (name "DONE_FF") (class "Default")
      (node (ref "E17") (pin "15") (pinfunction "Q_15") (pintype "output"))
      (node (ref "IC10") (pin "6") (pinfunction "I0_6") (pintype "input"))
    )
    (net (code "36") (name "DONE_SKIP") (class "Default")
      (node (ref "E18") (pin "10") (pinfunction "O_10") (pintype "output"))
      (node (ref "E20") (pin "5") (pinfunction "I1_5") (pintype "input"))
      (node (ref "E26") (pin "10") (pinfunction "I1_10") (pintype "input"))
    )
    (net (code "37") (name "ERROR") (class "Default")
      (node (ref "E26") (pin "4") (pinfunction "I0_4") (pintype "input"))
      (node (ref "E36") (pin "1") (pinfunction "O_1") (pintype "output"))
    )
    (net (code "38") (name "ERR_SKIP") (class "Default")
      (node (ref "E18") (pin "4") (pinfunction "O_4") (pintype "output"))
      (node (ref "E20") (pin "4") (pinfunction "I0_4") (pintype "input"))
      (node (ref "E26") (pin "5") (pinfunction "I1_5") (pintype "input"))
    )
    (net (code "39") (name "GND") (class "Default")
      (node (ref "C1") (pin "2") (pinfunction "2_2") (pintype "passive"))
      (node (ref "C10") (pin "2") (pinfunction "2_2") (pintype "passive"))
      (node (ref "C11") (pin "2") (pinfunction "2_2") (pintype "passive"))
      (node (ref "C12") (pin "2") (pinfunction "2_2") (pintype "passive"))
      (node (ref "C13") (pin "2") (pinfunction "2_2") (pintype "passive"))
      (node (ref "C14") (pin "2") (pinfunction "2_2") (pintype "passive"))
      (node (ref "C15") (pin "2") (pinfunction "2_2") (pintype "passive"))
      (node (ref "C16") (pin "2") (pinfunction "2_2") (pintype "passive"))
      (node (ref "C17") (pin "2") (pinfunction "2_2") (pintype "passive"))
      (node (ref "C18") (pin "2") (pinfunction "2_2") (pintype "passive"))
      (node (ref "C19") (pin "2") (pinfunction "2_2") (pintype "passive"))
      (node (ref "C2") (pin "2") (pinfunction "2_2") (pintype "passive"))
      (node (ref "C20") (pin "2") (pinfunction "2_2") (pintype "passive"))
      (node (ref "C21") (pin "2") (pinfunction "2_2") (pintype "passive"))
      (node (ref "C22") (pin "2") (pinfunction "2_2") (pintype "passive"))
      (node (ref "C23") (pin "2") (pinfunction "2_2") (pintype "passive"))
      (node (ref "C24") (pin "2") (pinfunction "2_2") (pintype "passive"))
      (node (ref "C25") (pin "2") (pinfunction "2_2") (pintype "passive"))
      (node (ref "C26") (pin "2") (pinfunction "2_2") (pintype "passive"))
      (node (ref "C27") (pin "2") (pinfunction "2_2") (pintype "passive"))
      (node (ref "C28") (pin "2") (pinfunction "2_2") (pintype "passive"))
      (node (ref "C29") (pin "2") (pinfunction "2_2") (pintype "passive"))
      (node (ref "C3") (pin "2") (pinfunction "2_2") (pintype "passive"))
      (node (ref "C30") (pin "2") (pinfunction "2_2") (pintype "passive"))
      (node (ref "C31") (pin "2") (pinfunction "2_2") (pintype "passive"))
      (node (ref "C32") (pin "2") (pinfunction "2_2") (pintype "passive"))
      (node (ref "C33") (pin "2") (pinfunction "2_2") (pintype "passive"))
      (node (ref "C34") (pin "2") (pinfunction "2_2") (pintype "passive"))
      (node (ref "C35") (pin "2") (pinfunction "2_2") (pintype "passive"))
      (node (ref "C36") (pin "2") (pinfunction "2_2") (pintype "passive"))
      (node (ref "C37") (pin "2") (pinfunction "2_2") (pintype "passive"))
      (node (ref "C38") (pin "2") (pinfunction "2_2") (pintype "passive"))
      (node (ref "C39") (pin "2") (pinfunction "2_2") (pintype "passive"))
      (node (ref "C4") (pin "2") (pinfunction "2_2") (pintype "passive"))
      (node (ref "C40") (pin "-") (pinfunction "-_-") (pintype "passive"))
      (node (ref "C5") (pin "2") (pinfunction "2_2") (pintype "passive"))
      (node (ref "C6") (pin "2") (pinfunction "2_2") (pintype "passive"))
      (node (ref "C7") (pin "2") (pinfunction "2_2") (pintype "passive"))
      (node (ref "C8") (pin "2") (pinfunction "2_2") (pintype "passive"))
      (node (ref "C9") (pin "2") (pinfunction "2_2") (pintype "passive"))
      (node (ref "D34L1") (pin "A") (pinfunction "1_A") (pintype "bidirectional"))
      (node (ref "D34L1") (pin "AA") (pinfunction "23_AA") (pintype "bidirectional"))
      (node (ref "D34L1") (pin "C") (pinfunction "3_C") (pintype "bidirectional"))
      (node (ref "D34L1") (pin "CC") (pinfunction "25_CC") (pintype "bidirectional"))
      (node (ref "D34L1") (pin "E") (pinfunction "5_E") (pintype "bidirectional"))
      (node (ref "D34L1") (pin "EE") (pinfunction "27_EE") (pintype "bidirectional"))
      (node (ref "D34L1") (pin "H") (pinfunction "7_H") (pintype "bidirectional"))
      (node (ref "D34L1") (pin "HH") (pinfunction "29_HH") (pintype "bidirectional"))
      (node (ref "D34L1") (pin "K") (pinfunction "9_K") (pintype "bidirectional"))
      (node (ref "D34L1") (pin "KK") (pinfunction "31_KK") (pintype "bidirectional"))
      (node (ref "D34L1") (pin "M") (pinfunction "11_M") (pintype "bidirectional"))
      (node (ref "D34L1") (pin "MM") (pinfunction "33_MM") (pintype "bidirectional"))
      (node (ref "D34L1") (pin "P") (pinfunction "13_P") (pintype "bidirectional"))
      (node (ref "D34L1") (pin "PP") (pinfunction "35_PP") (pintype "bidirectional"))
      (node (ref "D34L1") (pin "S") (pinfunction "15_S") (pintype "bidirectional"))
      (node (ref "D34L1") (pin "SS") (pinfunction "37_SS") (pintype "bidirectional"))
      (node (ref "D34L1") (pin "U") (pinfunction "17_U") (pintype "bidirectional"))
      (node (ref "D34L1") (pin "UU") (pinfunction "39_UU") (pintype "bidirectional"))
      (node (ref "D34L1") (pin "W") (pinfunction "19_W") (pintype "bidirectional"))
      (node (ref "D34L1") (pin "Y") (pinfunction "21_Y") (pintype "bidirectional"))
      (node (ref "D34L2") (pin "A") (pinfunction "1_A") (pintype "bidirectional"))
      (node (ref "D34L2") (pin "AA") (pinfunction "23_AA") (pintype "bidirectional"))
      (node (ref "D34L2") (pin "C") (pinfunction "3_C") (pintype "bidirectional"))
      (node (ref "D34L2") (pin "CC") (pinfunction "25_CC") (pintype "bidirectional"))
      (node (ref "D34L2") (pin "E") (pinfunction "5_E") (pintype "bidirectional"))
      (node (ref "D34L2") (pin "EE") (pinfunction "27_EE") (pintype "bidirectional"))
      (node (ref "D34L2") (pin "H") (pinfunction "7_H") (pintype "bidirectional"))
      (node (ref "D34L2") (pin "HH") (pinfunction "29_HH") (pintype "bidirectional"))
      (node (ref "D34L2") (pin "K") (pinfunction "9_K") (pintype "bidirectional"))
      (node (ref "D34L2") (pin "KK") (pinfunction "31_KK") (pintype "bidirectional"))
      (node (ref "D34L2") (pin "M") (pinfunction "11_M") (pintype "bidirectional"))
      (node (ref "D34L2") (pin "MM") (pinfunction "33_MM") (pintype "bidirectional"))
      (node (ref "D34L2") (pin "P") (pinfunction "13_P") (pintype "bidirectional"))
      (node (ref "D34L2") (pin "PP") (pinfunction "35_PP") (pintype "bidirectional"))
      (node (ref "D34L2") (pin "S") (pinfunction "15_S") (pintype "bidirectional"))
      (node (ref "D34L2") (pin "SS") (pinfunction "37_SS") (pintype "bidirectional"))
      (node (ref "D34L2") (pin "U") (pinfunction "17_U") (pintype "bidirectional"))
      (node (ref "D34L2") (pin "UU") (pinfunction "39_UU") (pintype "bidirectional"))
      (node (ref "D34L2") (pin "W") (pinfunction "19_W") (pintype "bidirectional"))
      (node (ref "D34L2") (pin "Y") (pinfunction "21_Y") (pintype "bidirectional"))
      (node (ref "D35L1") (pin "A") (pinfunction "1_A") (pintype "bidirectional"))
      (node (ref "D35L1") (pin "AA") (pinfunction "23_AA") (pintype "bidirectional"))
      (node (ref "D35L1") (pin "C") (pinfunction "3_C") (pintype "bidirectional"))
      (node (ref "D35L1") (pin "CC") (pinfunction "25_CC") (pintype "bidirectional"))
      (node (ref "D35L1") (pin "E") (pinfunction "5_E") (pintype "bidirectional"))
      (node (ref "D35L1") (pin "EE") (pinfunction "27_EE") (pintype "bidirectional"))
      (node (ref "D35L1") (pin "H") (pinfunction "7_H") (pintype "bidirectional"))
      (node (ref "D35L1") (pin "HH") (pinfunction "29_HH") (pintype "bidirectional"))
      (node (ref "D35L1") (pin "K") (pinfunction "9_K") (pintype "bidirectional"))
      (node (ref "D35L1") (pin "KK") (pinfunction "31_KK") (pintype "bidirectional"))
      (node (ref "D35L1") (pin "M") (pinfunction "11_M") (pintype "bidirectional"))
      (node (ref "D35L1") (pin "MM") (pinfunction "33_MM") (pintype "bidirectional"))
      (node (ref "D35L1") (pin "P") (pinfunction "13_P") (pintype "bidirectional"))
      (node (ref "D35L1") (pin "PP") (pinfunction "35_PP") (pintype "bidirectional"))
      (node (ref "D35L1") (pin "S") (pinfunction "15_S") (pintype "bidirectional"))
      (node (ref "D35L1") (pin "SS") (pinfunction "37_SS") (pintype "bidirectional"))
      (node (ref "D35L1") (pin "U") (pinfunction "17_U") (pintype "bidirectional"))
      (node (ref "D35L1") (pin "UU") (pinfunction "39_UU") (pintype "bidirectional"))
      (node (ref "D35L1") (pin "W") (pinfunction "19_W") (pintype "bidirectional"))
      (node (ref "D35L1") (pin "Y") (pinfunction "21_Y") (pintype "bidirectional"))
      (node (ref "D35L2") (pin "A") (pinfunction "1_A") (pintype "bidirectional"))
      (node (ref "D35L2") (pin "AA") (pinfunction "23_AA") (pintype "bidirectional"))
      (node (ref "D35L2") (pin "C") (pinfunction "3_C") (pintype "bidirectional"))
      (node (ref "D35L2") (pin "CC") (pinfunction "25_CC") (pintype "bidirectional"))
      (node (ref "D35L2") (pin "E") (pinfunction "5_E") (pintype "bidirectional"))
      (node (ref "D35L2") (pin "EE") (pinfunction "27_EE") (pintype "bidirectional"))
      (node (ref "D35L2") (pin "H") (pinfunction "7_H") (pintype "bidirectional"))
      (node (ref "D35L2") (pin "HH") (pinfunction "29_HH") (pintype "bidirectional"))
      (node (ref "D35L2") (pin "K") (pinfunction "9_K") (pintype "bidirectional"))
      (node (ref "D35L2") (pin "KK") (pinfunction "31_KK") (pintype "bidirectional"))
      (node (ref "D35L2") (pin "M") (pinfunction "11_M") (pintype "bidirectional"))
      (node (ref "D35L2") (pin "MM") (pinfunction "33_MM") (pintype "bidirectional"))
      (node (ref "D35L2") (pin "P") (pinfunction "13_P") (pintype "bidirectional"))
      (node (ref "D35L2") (pin "PP") (pinfunction "35_PP") (pintype "bidirectional"))
      (node (ref "D35L2") (pin "S") (pinfunction "15_S") (pintype "bidirectional"))
      (node (ref "D35L2") (pin "SS") (pinfunction "37_SS") (pintype "bidirectional"))
      (node (ref "D35L2") (pin "U") (pinfunction "17_U") (pintype "bidirectional"))
      (node (ref "D35L2") (pin "UU") (pinfunction "39_UU") (pintype "bidirectional"))
      (node (ref "D35L2") (pin "W") (pinfunction "19_W") (pintype "bidirectional"))
      (node (ref "D35L2") (pin "Y") (pinfunction "21_Y") (pintype "bidirectional"))
      (node (ref "D36L1") (pin "A") (pinfunction "1_A") (pintype "bidirectional"))
      (node (ref "D36L1") (pin "AA") (pinfunction "23_AA") (pintype "bidirectional"))
      (node (ref "D36L1") (pin "C") (pinfunction "3_C") (pintype "bidirectional"))
      (node (ref "D36L1") (pin "CC") (pinfunction "25_CC") (pintype "bidirectional"))
      (node (ref "D36L1") (pin "E") (pinfunction "5_E") (pintype "bidirectional"))
      (node (ref "D36L1") (pin "EE") (pinfunction "27_EE") (pintype "bidirectional"))
      (node (ref "D36L1") (pin "H") (pinfunction "7_H") (pintype "bidirectional"))
      (node (ref "D36L1") (pin "HH") (pinfunction "29_HH") (pintype "bidirectional"))
      (node (ref "D36L1") (pin "K") (pinfunction "9_K") (pintype "bidirectional"))
      (node (ref "D36L1") (pin "KK") (pinfunction "31_KK") (pintype "bidirectional"))
      (node (ref "D36L1") (pin "M") (pinfunction "11_M") (pintype "bidirectional"))
      (node (ref "D36L1") (pin "MM") (pinfunction "33_MM") (pintype "bidirectional"))
      (node (ref "D36L1") (pin "P") (pinfunction "13_P") (pintype "bidirectional"))
      (node (ref "D36L1") (pin "PP") (pinfunction "35_PP") (pintype "bidirectional"))
      (node (ref "D36L1") (pin "S") (pinfunction "15_S") (pintype "bidirectional"))
      (node (ref "D36L1") (pin "SS") (pinfunction "37_SS") (pintype "bidirectional"))
      (node (ref "D36L1") (pin "U") (pinfunction "17_U") (pintype "bidirectional"))
      (node (ref "D36L1") (pin "UU") (pinfunction "39_UU") (pintype "bidirectional"))
      (node (ref "D36L1") (pin "W") (pinfunction "19_W") (pintype "bidirectional"))
      (node (ref "D36L1") (pin "Y") (pinfunction "21_Y") (pintype "bidirectional"))
      (node (ref "D36L2") (pin "A") (pinfunction "1_A") (pintype "bidirectional"))
      (node (ref "D36L2") (pin "AA") (pinfunction "23_AA") (pintype "bidirectional"))
      (node (ref "D36L2") (pin "C") (pinfunction "3_C") (pintype "bidirectional"))
      (node (ref "D36L2") (pin "CC") (pinfunction "25_CC") (pintype "bidirectional"))
      (node (ref "D36L2") (pin "E") (pinfunction "5_E") (pintype "bidirectional"))
      (node (ref "D36L2") (pin "EE") (pinfunction "27_EE") (pintype "bidirectional"))
      (node (ref "D36L2") (pin "H") (pinfunction "7_H") (pintype "bidirectional"))
      (node (ref "D36L2") (pin "HH") (pinfunction "29_HH") (pintype "bidirectional"))
      (node (ref "D36L2") (pin "K") (pinfunction "9_K") (pintype "bidirectional"))
      (node (ref "D36L2") (pin "KK") (pinfunction "31_KK") (pintype "bidirectional"))
      (node (ref "D36L2") (pin "M") (pinfunction "11_M") (pintype "bidirectional"))
      (node (ref "D36L2") (pin "MM") (pinfunction "33_MM") (pintype "bidirectional"))
      (node (ref "D36L2") (pin "P") (pinfunction "13_P") (pintype "bidirectional"))
      (node (ref "D36L2") (pin "PP") (pinfunction "35_PP") (pintype "bidirectional"))
      (node (ref "D36L2") (pin "S") (pinfunction "15_S") (pintype "bidirectional"))
      (node (ref "D36L2") (pin "SS") (pinfunction "37_SS") (pintype "bidirectional"))
      (node (ref "D36L2") (pin "U") (pinfunction "17_U") (pintype "bidirectional"))
      (node (ref "D36L2") (pin "UU") (pinfunction "39_UU") (pintype "bidirectional"))
      (node (ref "D36L2") (pin "W") (pinfunction "19_W") (pintype "bidirectional"))
      (node (ref "D36L2") (pin "Y") (pinfunction "21_Y") (pintype "bidirectional"))
      (node (ref "DRIVE") (pin "A") (pinfunction "1_A") (pintype "bidirectional"))
      (node (ref "DRIVE") (pin "AA") (pinfunction "23_AA") (pintype "bidirectional"))
      (node (ref "DRIVE") (pin "B") (pinfunction "2_B") (pintype "bidirectional"))
      (node (ref "DRIVE") (pin "C") (pinfunction "3_C") (pintype "bidirectional"))
      (node (ref "DRIVE") (pin "CC") (pinfunction "25_CC") (pintype "bidirectional"))
      (node (ref "DRIVE") (pin "DD") (pinfunction "26_DD") (pintype "bidirectional"))
      (node (ref "DRIVE") (pin "E") (pinfunction "5_E") (pintype "bidirectional"))
      (node (ref "DRIVE") (pin "EE") (pinfunction "27_EE") (pintype "bidirectional"))
      (node (ref "DRIVE") (pin "F") (pinfunction "6_F") (pintype "bidirectional"))
      (node (ref "DRIVE") (pin "H") (pinfunction "7_H") (pintype "bidirectional"))
      (node (ref "DRIVE") (pin "HH") (pinfunction "29_HH") (pintype "bidirectional"))
      (node (ref "DRIVE") (pin "JJ") (pinfunction "30_JJ") (pintype "bidirectional"))
      (node (ref "DRIVE") (pin "K") (pinfunction "9_K") (pintype "bidirectional"))
      (node (ref "DRIVE") (pin "KK") (pinfunction "31_KK") (pintype "bidirectional"))
      (node (ref "DRIVE") (pin "L") (pinfunction "10_L") (pintype "bidirectional"))
      (node (ref "DRIVE") (pin "M") (pinfunction "11_M") (pintype "bidirectional"))
      (node (ref "DRIVE") (pin "MM") (pinfunction "33_MM") (pintype "bidirectional"))
      (node (ref "DRIVE") (pin "NN") (pinfunction "34_NN") (pintype "bidirectional"))
      (node (ref "DRIVE") (pin "P") (pinfunction "13_P") (pintype "bidirectional"))
      (node (ref "DRIVE") (pin "PP") (pinfunction "35_PP") (pintype "bidirectional"))
      (node (ref "DRIVE") (pin "R") (pinfunction "14_R") (pintype "bidirectional"))
      (node (ref "DRIVE") (pin "S") (pinfunction "15_S") (pintype "bidirectional"))
      (node (ref "DRIVE") (pin "SS") (pinfunction "37_SS") (pintype "bidirectional"))
      (node (ref "DRIVE") (pin "TT") (pinfunction "38_TT") (pintype "bidirectional"))
      (node (ref "DRIVE") (pin "U") (pinfunction "17_U") (pintype "bidirectional"))
      (node (ref "DRIVE") (pin "UU") (pinfunction "39_UU") (pintype "bidirectional"))
      (node (ref "DRIVE") (pin "V") (pinfunction "18_V") (pintype "bidirectional"))
      (node (ref "DRIVE") (pin "VV") (pinfunction "40_VV") (pintype "bidirectional"))
      (node (ref "DRIVE") (pin "W") (pinfunction "19_W") (pintype "bidirectional"))
      (node (ref "DRIVE") (pin "Y") (pinfunction "21_Y") (pintype "bidirectional"))
      (node (ref "DRIVE") (pin "Z") (pinfunction "22_Z") (pintype "bidirectional"))
      (node (ref "E11") (pin "5") (pinfunction "G2B_5") (pintype "input"))
      (node (ref "E12") (pin "5") (pinfunction "G2B_5") (pintype "input"))
      (node (ref "E13") (pin "5") (pinfunction "G2B_5") (pintype "input"))
      (node (ref "E2") (pin "2") (pinfunction "D_2") (pintype "input"))
      (node (ref "E4") (pin "6") (pinfunction "D_6") (pintype "input"))
      (node (ref "LASTDEV") (pin "1") (pinfunction "1_1") (pintype "passive"))
      (node (ref "R10") (pin "1") (pinfunction "1_1") (pintype "passive"))
      (node (ref "R11") (pin "1") (pinfunction "1_1") (pintype "passive"))
      (node (ref "R12") (pin "1") (pinfunction "1_1") (pintype "passive"))
      (node (ref "R13") (pin "1") (pinfunction "1_1") (pintype "passive"))
      (node (ref "R14") (pin "1") (pinfunction "1_1") (pintype "passive"))
      (node (ref "R15") (pin "1") (pinfunction "1_1") (pintype "passive"))
      (node (ref "R16") (pin "1") (pinfunction "1_1") (pintype "passive"))
      (node (ref "R17") (pin "1") (pinfunction "1_1") (pintype "passive"))
      (node (ref "SL1") (pin "2") (pinfunction "S_2") (pintype "passive"))
      (node (ref "SL1") (pin "3") (pinfunction "S_3") (pintype "passive"))
    )
    (net (code "40") (name "INIT") (class "Default")
      (node (ref "E1") (pin "8") (pinfunction "O_8") (pintype "output"))
      (node (ref "E15") (pin "4") (pinfunction "I0_4") (pintype "input"))
      (node (ref "E15") (pin "5") (pinfunction "I1_5") (pintype "input"))
      (node (ref "E18") (pin "12") (pinfunction "I1_12") (pintype "input"))
      (node (ref "IC8") (pin "6") (pinfunction "I0_6") (pintype "input"))
      (node (ref "IC8") (pin "7") (pinfunction "I1_7") (pintype "input"))
    )
    (net (code "41") (name "MAINT") (class "Default")
      (node (ref "E16") (pin "9") (pinfunction "Q_9") (pintype "output"))
      (node (ref "E32") (pin "9") (pinfunction "I0_9") (pintype "input"))
      (node (ref "E35") (pin "3") (pinfunction "I1_3") (pintype "input"))
      (node (ref "E35") (pin "6") (pinfunction "I1_6") (pintype "input"))
      (node (ref "E35") (pin "9") (pinfunction "I1_9") (pintype "input"))
      (node (ref "E36") (pin "2") (pinfunction "I0_2") (pintype "input"))
      (node (ref "E36") (pin "6") (pinfunction "I1_6") (pintype "input"))
      (node (ref "E36") (pin "9") (pinfunction "I1_9") (pintype "input"))
    )
    (net (code "42") (name "MSB8") (class "Default")
      (node (ref "E21") (pin "12") (pinfunction "QD_12") (pintype "output"))
      (node (ref "E23") (pin "2") (pinfunction "J_2") (pintype "input"))
      (node (ref "E23") (pin "3") (pinfunction "K_3") (pintype "input"))
      (node (ref "E8") (pin "5") (pinfunction "I2_5") (pintype "input"))
      (node (ref "IC1") (pin "6") (pinfunction "I0_6") (pintype "input"))
    )
    (net (code "43") (name "MSB12") (class "Default")
      (node (ref "E23") (pin "12") (pinfunction "QD_12") (pintype "output"))
      (node (ref "E8") (pin "2") (pinfunction "I1_2") (pintype "input"))
      (node (ref "IC6") (pin "1") (pinfunction "I0_1") (pintype "input"))
    )
    (net (code "44") (name "Net-(70-P)") (class "Default")
      (node (ref "70") (pin "1") (pinfunction "P_1") (pintype "passive"))
      (node (ref "E14") (pin "15") (pinfunction "Y0_15") (pintype "output"))
    )
    (net (code "45") (name "Net-(71-P)") (class "Default")
      (node (ref "71") (pin "1") (pinfunction "P_1") (pintype "passive"))
      (node (ref "E14") (pin "14") (pinfunction "Y1_14") (pintype "output"))
    )
    (net (code "46") (name "Net-(72-P)") (class "Default")
      (node (ref "72") (pin "1") (pinfunction "P_1") (pintype "passive"))
      (node (ref "E14") (pin "13") (pinfunction "Y2_13") (pintype "output"))
    )
    (net (code "47") (name "Net-(73-P)") (class "Default")
      (node (ref "73") (pin "1") (pinfunction "P_1") (pintype "passive"))
      (node (ref "E14") (pin "12") (pinfunction "Y3_12") (pintype "output"))
    )
    (net (code "48") (name "Net-(74-P)") (class "Default")
      (node (ref "74") (pin "1") (pinfunction "P_1") (pintype "passive"))
      (node (ref "E14") (pin "11") (pinfunction "Y4_11") (pintype "output"))
    )
    (net (code "49") (name "Net-(75-P)") (class "Default")
      (node (ref "75") (pin "1") (pinfunction "P_1") (pintype "passive"))
      (node (ref "E14") (pin "10") (pinfunction "Y5_10") (pintype "output"))
    )
    (net (code "50") (name "Net-(76-P)") (class "Default")
      (node (ref "76") (pin "1") (pinfunction "P_1") (pintype "passive"))
      (node (ref "E14") (pin "9") (pinfunction "Y6_9") (pintype "output"))
    )
    (net (code "51") (name "Net-(77-P)") (class "Default")
      (node (ref "77") (pin "1") (pinfunction "P_1") (pintype "passive"))
      (node (ref "E14") (pin "7") (pinfunction "Y7_7") (pintype "output"))
    )
    (net (code "52") (name "Net-(E1B-O)") (class "Default")
      (node (ref "E1") (pin "10") (pinfunction "I1_10") (pintype "input"))
      (node (ref "E1") (pin "6") (pinfunction "O_6") (pintype "output"))
      (node (ref "E1") (pin "9") (pinfunction "I0_9") (pintype "input"))
      (node (ref "E2") (pin "1") (pinfunction "CLR_1") (pintype "input"))
    )
    (net (code "53") (name "Net-(E1C-I2)") (class "Default")
      (node (ref "E1") (pin "11") (pinfunction "I2_11") (pintype "input"))
      (node (ref "E2") (pin "6") (pinfunction "~{Q}_6") (pintype "output"))
    )
    (net (code "54") (name "Net-(E4A-A)") (class "Default")
      (node (ref "E4") (pin "10") (pinfunction "ENT_10") (pintype "input"))
      (node (ref "E4") (pin "3") (pinfunction "A_3") (pintype "input"))
      (node (ref "E4") (pin "4") (pinfunction "B_4") (pintype "input"))
      (node (ref "E4") (pin "7") (pinfunction "ENP_7") (pintype "input"))
      (node (ref "R19") (pin "2") (pinfunction "2_2") (pintype "passive"))
    )
    (net (code "55") (name "Net-(E4A-C)") (class "Default")
      (node (ref "E4") (pin "5") (pinfunction "C_5") (pintype "input"))
      (node (ref "E5") (pin "3") (pinfunction "O_3") (pintype "output"))
    )
    (net (code "56") (name "Net-(E5A-I0)") (class "Default")
      (node (ref "E5") (pin "1") (pinfunction "I0_1") (pintype "input"))
      (node (ref "E5") (pin "11") (pinfunction "O_11") (pintype "output"))
    )
    (net (code "57") (name "Net-(E8A-O)") (class "Default")
      (node (ref "E8") (pin "11") (pinfunction "I2_11") (pintype "input"))
      (node (ref "E8") (pin "12") (pinfunction "O_12") (pintype "output"))
    )
    (net (code "58") (name "Net-(E8B-O)") (class "Default")
      (node (ref "E8") (pin "6") (pinfunction "O_6") (pintype "output"))
      (node (ref "E8") (pin "9") (pinfunction "I0_9") (pintype "input"))
    )
    (net (code "59") (name "Net-(E10A-I0)") (class "Default")
      (node (ref "E10") (pin "1") (pinfunction "I0_1") (pintype "input"))
      (node (ref "E10") (pin "6") (pinfunction "O_6") (pintype "output"))
    )
    (net (code "60") (name "Net-(E10A-O)") (class "Default")
      (node (ref "E10") (pin "10") (pinfunction "I1_10") (pintype "input"))
      (node (ref "E10") (pin "11") (pinfunction "I2_11") (pintype "input"))
      (node (ref "E10") (pin "12") (pinfunction "O_12") (pintype "output"))
    )
    (net (code "61") (name "Net-(E10C-O)") (class "Default")
      (node (ref "E10") (pin "8") (pinfunction "O_8") (pintype "output"))
      (node (ref "IC7") (pin "1") (pinfunction "I0_1") (pintype "input"))
      (node (ref "IC7") (pin "2") (pinfunction "I1_2") (pintype "input"))
    )
    (net (code "62") (name "Net-(E14A-G2A)") (class "Default")
      (node (ref "E1") (pin "12") (pinfunction "O_12") (pintype "output"))
      (node (ref "E14") (pin "4") (pinfunction "G2A_4") (pintype "input"))
      (node (ref "E14") (pin "5") (pinfunction "G2B_5") (pintype "input"))
    )
    (net (code "63") (name "Net-(E15A-O)") (class "Default")
      (node (ref "E15") (pin "3") (pinfunction "O_3") (pintype "output"))
      (node (ref "E8") (pin "13") (pinfunction "I2_13") (pintype "input"))
      (node (ref "E8") (pin "3") (pinfunction "I0_3") (pintype "input"))
    )
    (net (code "64") (name "Net-(E15C-I0)") (class "Default")
      (node (ref "E15") (pin "9") (pinfunction "I0_9") (pintype "input"))
      (node (ref "E20") (pin "11") (pinfunction "O_11") (pintype "output"))
      (node (ref "E24") (pin "10") (pinfunction "I1_10") (pintype "input"))
    )
    (net (code "65") (name "Net-(E15C-O)") (class "Default")
      (node (ref "E15") (pin "8") (pinfunction "O_8") (pintype "output"))
      (node (ref "E24") (pin "12") (pinfunction "I0_12") (pintype "input"))
    )
    (net (code "66") (name "Net-(E15D-O)") (class "Default")
      (node (ref "E15") (pin "11") (pinfunction "O_11") (pintype "output"))
      (node (ref "E8") (pin "10") (pinfunction "I1_10") (pintype "input"))
    )
    (net (code "67") (name "Net-(E17A-CLK)") (class "Default")
      (node (ref "E17") (pin "1") (pinfunction "CLK_1") (pintype "input"))
      (node (ref "IC11") (pin "6") (pinfunction "O_6") (pintype "output"))
    )
    (net (code "68") (name "Net-(E17A-~{Q})") (class "Default")
      (node (ref "E17") (pin "14") (pinfunction "~{Q}_14") (pintype "output"))
      (node (ref "E18") (pin "9") (pinfunction "I1_9") (pintype "input"))
    )
    (net (code "69") (name "Net-(E17B-CLR)") (class "Default")
      (node (ref "E17") (pin "8") (pinfunction "CLR_8") (pintype "input"))
      (node (ref "E18") (pin "13") (pinfunction "O_13") (pintype "output"))
    )
    (net (code "70") (name "Net-(E17B-J)") (class "Default")
      (node (ref "E17") (pin "12") (pinfunction "K_12") (pintype "input"))
      (node (ref "E17") (pin "9") (pinfunction "J_9") (pintype "input"))
      (node (ref "E8") (pin "8") (pinfunction "O_8") (pintype "output"))
      (node (ref "IC7") (pin "7") (pinfunction "I1_7") (pintype "input"))
    )
    (net (code "71") (name "Net-(E18A-I1)") (class "Default")
      (node (ref "E18") (pin "3") (pinfunction "I1_3") (pintype "input"))
      (node (ref "E19") (pin "14") (pinfunction "~{Q}_14") (pintype "output"))
    )
    (net (code "72") (name "Net-(E18B-I1)") (class "Default")
      (node (ref "E18") (pin "6") (pinfunction "I1_6") (pintype "input"))
      (node (ref "E19") (pin "10") (pinfunction "~{Q}_10") (pintype "output"))
    )
    (net (code "73") (name "Net-(E19A-CLK)") (class "Default")
      (node (ref "E19") (pin "1") (pinfunction "CLK_1") (pintype "input"))
      (node (ref "IC11") (pin "2") (pinfunction "O_2") (pintype "output"))
    )
    (net (code "74") (name "Net-(E19B-CLK)") (class "Default")
      (node (ref "E19") (pin "6") (pinfunction "CLK_6") (pintype "input"))
      (node (ref "IC11") (pin "4") (pinfunction "O_4") (pintype "output"))
    )
    (net (code "75") (name "Net-(E20A-I1)") (class "Default")
      (node (ref "E20") (pin "2") (pinfunction "I1_2") (pintype "input"))
      (node (ref "E20") (pin "6") (pinfunction "O_6") (pintype "output"))
    )
    (net (code "76") (name "Net-(E20A-O)") (class "Default")
      (node (ref "E20") (pin "3") (pinfunction "O_3") (pintype "output"))
      (node (ref "IC10") (pin "1") (pinfunction "I0_1") (pintype "input"))
      (node (ref "IC10") (pin "2") (pinfunction "I1_2") (pintype "input"))
    )
    (net (code "77") (name "Net-(E21A-J)") (class "Default")
      (node (ref "E21") (pin "2") (pinfunction "J_2") (pintype "input"))
      (node (ref "E21") (pin "3") (pinfunction "K_3") (pintype "input"))
      (node (ref "E22") (pin "12") (pinfunction "QD_12") (pintype "output"))
      (node (ref "IC4") (pin "6") (pinfunction "I0_6") (pintype "input"))
    )
    (net (code "78") (name "Net-(E21A-QA)") (class "Default")
      (node (ref "E21") (pin "15") (pinfunction "QA_15") (pintype "output"))
      (node (ref "IC3") (pin "6") (pinfunction "I0_6") (pintype "input"))
    )
    (net (code "79") (name "Net-(E21A-QB)") (class "Default")
      (node (ref "E21") (pin "14") (pinfunction "QB_14") (pintype "output"))
      (node (ref "IC3") (pin "1") (pinfunction "I0_1") (pintype "input"))
    )
    (net (code "80") (name "Net-(E21A-QC)") (class "Default")
      (node (ref "E21") (pin "13") (pinfunction "QC_13") (pintype "output"))
      (node (ref "IC4") (pin "1") (pinfunction "I0_1") (pintype "input"))
    )
    (net (code "81") (name "Net-(E22A-QA)") (class "Default")
      (node (ref "E22") (pin "15") (pinfunction "QA_15") (pintype "output"))
      (node (ref "IC2") (pin "1") (pinfunction "I0_1") (pintype "input"))
    )
    (net (code "82") (name "Net-(E22A-QB)") (class "Default")
      (node (ref "E22") (pin "14") (pinfunction "QB_14") (pintype "output"))
      (node (ref "IC5") (pin "6") (pinfunction "I0_6") (pintype "input"))
    )
    (net (code "83") (name "Net-(E22A-QC)") (class "Default")
      (node (ref "E22") (pin "13") (pinfunction "QC_13") (pintype "output"))
      (node (ref "IC5") (pin "1") (pinfunction "I0_1") (pintype "input"))
    )
    (net (code "84") (name "Net-(E23A-QA)") (class "Default")
      (node (ref "E23") (pin "15") (pinfunction "QA_15") (pintype "output"))
      (node (ref "IC2") (pin "6") (pinfunction "I0_6") (pintype "input"))
    )
    (net (code "85") (name "Net-(E23A-QB)") (class "Default")
      (node (ref "E23") (pin "14") (pinfunction "QB_14") (pintype "output"))
      (node (ref "IC1") (pin "1") (pinfunction "I0_1") (pintype "input"))
    )
    (net (code "86") (name "Net-(E23A-QC)") (class "Default")
      (node (ref "E23") (pin "13") (pinfunction "QC_13") (pintype "output"))
      (node (ref "IC6") (pin "6") (pinfunction "I0_6") (pintype "input"))
    )
    (net (code "87") (name "Net-(E24A-I1)") (class "Default")
      (node (ref "E24") (pin "2") (pinfunction "I1_2") (pintype "input"))
      (node (ref "E35") (pin "13") (pinfunction "O_13") (pintype "output"))
      (node (ref "IC1") (pin "7") (pinfunction "I1_7") (pintype "input"))
      (node (ref "IC2") (pin "2") (pinfunction "I1_2") (pintype "input"))
      (node (ref "IC3") (pin "2") (pinfunction "I1_2") (pintype "input"))
      (node (ref "IC3") (pin "7") (pinfunction "I1_7") (pintype "input"))
      (node (ref "IC4") (pin "2") (pinfunction "I1_2") (pintype "input"))
      (node (ref "IC4") (pin "7") (pinfunction "I1_7") (pintype "input"))
      (node (ref "IC5") (pin "2") (pinfunction "I1_2") (pintype "input"))
      (node (ref "IC5") (pin "7") (pinfunction "I1_7") (pintype "input"))
    )
    (net (code "88") (name "Net-(E24A-O)") (class "Default")
      (node (ref "E24") (pin "3") (pinfunction "O_3") (pintype "output"))
      (node (ref "IC1") (pin "2") (pinfunction "I1_2") (pintype "input"))
      (node (ref "IC2") (pin "7") (pinfunction "I1_7") (pintype "input"))
      (node (ref "IC6") (pin "2") (pinfunction "I1_2") (pintype "input"))
      (node (ref "IC6") (pin "7") (pinfunction "I1_7") (pintype "input"))
    )
    (net (code "89") (name "Net-(E24B-O)") (class "Default")
      (node (ref "E24") (pin "6") (pinfunction "O_6") (pintype "output"))
      (node (ref "E32") (pin "1") (pinfunction "I0_1") (pintype "input"))
    )
    (net (code "90") (name "Net-(E24C-O)") (class "Default")
      (node (ref "E24") (pin "8") (pinfunction "O_8") (pintype "output"))
      (node (ref "E30") (pin "13") (pinfunction "CLR_13") (pintype "input"))
    )
    (net (code "91") (name "Net-(E25C-O)") (class "Default")
      (node (ref "E25") (pin "6") (pinfunction "O_6") (pintype "output"))
      (node (ref "E31") (pin "1") (pinfunction "I0_1") (pintype "input"))
      (node (ref "E31") (pin "2") (pinfunction "I1_2") (pintype "input"))
    )
    (net (code "92") (name "Net-(E25D-O)") (class "Default")
      (node (ref "E25") (pin "8") (pinfunction "O_8") (pintype "output"))
      (node (ref "E31") (pin "13") (pinfunction "I3_13") (pintype "input"))
    )
    (net (code "93") (name "Net-(E25E-O)") (class "Default")
      (node (ref "E25") (pin "10") (pinfunction "O_10") (pintype "output"))
      (node (ref "E26") (pin "12") (pinfunction "I0_12") (pintype "input"))
      (node (ref "E26") (pin "13") (pinfunction "I1_13") (pintype "input"))
    )
    (net (code "94") (name "Net-(E25F-O)") (class "Default")
      (node (ref "E25") (pin "12") (pinfunction "O_12") (pintype "output"))
      (node (ref "E36") (pin "11") (pinfunction "I0_11") (pintype "input"))
      (node (ref "E36") (pin "12") (pinfunction "I1_12") (pintype "input"))
    )
    (net (code "95") (name "Net-(E26A-O)") (class "Default")
      (node (ref "E26") (pin "3") (pinfunction "O_3") (pintype "output"))
      (node (ref "IC11") (pin "1") (pinfunction "I_1") (pintype "input"))
    )
    (net (code "96") (name "Net-(E26B-O)") (class "Default")
      (node (ref "E26") (pin "6") (pinfunction "O_6") (pintype "output"))
      (node (ref "IC11") (pin "3") (pinfunction "I_3") (pintype "input"))
    )
    (net (code "97") (name "Net-(E26C-O)") (class "Default")
      (node (ref "E26") (pin "8") (pinfunction "O_8") (pintype "output"))
      (node (ref "IC11") (pin "5") (pinfunction "I_5") (pintype "input"))
    )
    (net (code "98") (name "Net-(E30A-Q)") (class "Default")
      (node (ref "E30") (pin "5") (pinfunction "Q_5") (pintype "output"))
      (node (ref "IC10") (pin "7") (pinfunction "I1_7") (pintype "input"))
    )
    (net (code "99") (name "Net-(E30B-CLK)") (class "Default")
      (node (ref "E30") (pin "11") (pinfunction "CLK_11") (pintype "input"))
      (node (ref "IC9") (pin "3") (pinfunction "O_3") (pintype "open_collector"))
      (node (ref "R18") (pin "1") (pinfunction "1_1") (pintype "passive"))
    )
    (net (code "100") (name "Net-(E31A-O)") (class "Default")
      (node (ref "E31") (pin "6") (pinfunction "O_6") (pintype "output"))
      (node (ref "IC9") (pin "1") (pinfunction "I0_1") (pintype "input"))
    )
    (net (code "101") (name "Net-(E31B-O)") (class "Default")
      (node (ref "E31") (pin "8") (pinfunction "O_8") (pintype "output"))
      (node (ref "IC9") (pin "2") (pinfunction "I1_2") (pintype "input"))
    )
    (net (code "102") (name "Net-(E32A-O)") (class "Default")
      (node (ref "E32") (pin "12") (pinfunction "O_12") (pintype "output"))
      (node (ref "E32") (pin "4") (pinfunction "I1_4") (pintype "input"))
      (node (ref "E32") (pin "5") (pinfunction "I2_5") (pintype "input"))
    )
    (net (code "103") (name "Net-(E32C-O)") (class "Default")
      (node (ref "E32") (pin "8") (pinfunction "O_8") (pintype "output"))
      (node (ref "E35") (pin "11") (pinfunction "I0_11") (pintype "input"))
    )
    (net (code "104") (name "Net-(PAD10-P)") (class "Default")
      (node (ref "E38") (pin "1") (pinfunction "1_1") (pintype "passive"))
      (node (ref "PAD10") (pin "1") (pinfunction "P_1") (pintype "passive"))
    )
    (net (code "105") (name "Net-(PAD11-P)") (class "Default")
      (node (ref "E38") (pin "2") (pinfunction "2_2") (pintype "passive"))
      (node (ref "PAD11") (pin "1") (pinfunction "P_1") (pintype "passive"))
    )
    (net (code "106") (name "Net-(PAD12-P)") (class "Default")
      (node (ref "E38") (pin "3") (pinfunction "3_3") (pintype "passive"))
      (node (ref "PAD12") (pin "1") (pinfunction "P_1") (pintype "passive"))
    )
    (net (code "107") (name "Net-(PAD13-P)") (class "Default")
      (node (ref "E38") (pin "4") (pinfunction "4_4") (pintype "passive"))
      (node (ref "PAD13") (pin "1") (pinfunction "P_1") (pintype "passive"))
    )
    (net (code "108") (name "Net-(PAD14-P)") (class "Default")
      (node (ref "E38") (pin "5") (pinfunction "5_5") (pintype "passive"))
      (node (ref "PAD14") (pin "1") (pinfunction "P_1") (pintype "passive"))
    )
    (net (code "109") (name "Net-(PAD15-P)") (class "Default")
      (node (ref "E38") (pin "6") (pinfunction "6_6") (pintype "passive"))
      (node (ref "PAD15") (pin "1") (pinfunction "P_1") (pintype "passive"))
    )
    (net (code "110") (name "Net-(PAD16-P)") (class "Default")
      (node (ref "E38") (pin "7") (pinfunction "7_7") (pintype "passive"))
      (node (ref "PAD16") (pin "1") (pinfunction "P_1") (pintype "passive"))
    )
    (net (code "111") (name "Net-(PAD17-P)") (class "Default")
      (node (ref "E38") (pin "8") (pinfunction "8_8") (pintype "passive"))
      (node (ref "PAD17") (pin "1") (pinfunction "P_1") (pintype "passive"))
    )
    (net (code "112") (name "Net-(PAD18-P)") (class "Default")
      (node (ref "E40") (pin "1") (pinfunction "1_1") (pintype "passive"))
      (node (ref "PAD18") (pin "1") (pinfunction "P_1") (pintype "passive"))
    )
    (net (code "113") (name "Net-(PAD19-P)") (class "Default")
      (node (ref "E40") (pin "2") (pinfunction "2_2") (pintype "passive"))
      (node (ref "PAD19") (pin "1") (pinfunction "P_1") (pintype "passive"))
    )
    (net (code "114") (name "Net-(PAD20-P)") (class "Default")
      (node (ref "E38") (pin "16") (pinfunction "16_16") (pintype "passive"))
      (node (ref "PAD20") (pin "1") (pinfunction "P_1") (pintype "passive"))
    )
    (net (code "115") (name "Net-(PAD21-P)") (class "Default")
      (node (ref "E38") (pin "15") (pinfunction "15_15") (pintype "passive"))
      (node (ref "PAD21") (pin "1") (pinfunction "P_1") (pintype "passive"))
    )
    (net (code "116") (name "Net-(PAD22-P)") (class "Default")
      (node (ref "E38") (pin "14") (pinfunction "14_14") (pintype "passive"))
      (node (ref "PAD22") (pin "1") (pinfunction "P_1") (pintype "passive"))
    )
    (net (code "117") (name "Net-(PAD23-P)") (class "Default")
      (node (ref "E38") (pin "13") (pinfunction "13_13") (pintype "passive"))
      (node (ref "PAD23") (pin "1") (pinfunction "P_1") (pintype "passive"))
    )
    (net (code "118") (name "Net-(PAD24-P)") (class "Default")
      (node (ref "E38") (pin "12") (pinfunction "12_12") (pintype "passive"))
      (node (ref "PAD24") (pin "1") (pinfunction "P_1") (pintype "passive"))
    )
    (net (code "119") (name "Net-(PAD25-P)") (class "Default")
      (node (ref "E38") (pin "11") (pinfunction "11_11") (pintype "passive"))
      (node (ref "PAD25") (pin "1") (pinfunction "P_1") (pintype "passive"))
    )
    (net (code "120") (name "Net-(PAD26-P)") (class "Default")
      (node (ref "E38") (pin "10") (pinfunction "10_10") (pintype "passive"))
      (node (ref "PAD26") (pin "1") (pinfunction "P_1") (pintype "passive"))
    )
    (net (code "121") (name "Net-(PAD27-P)") (class "Default")
      (node (ref "E38") (pin "9") (pinfunction "9_9") (pintype "passive"))
      (node (ref "PAD27") (pin "1") (pinfunction "P_1") (pintype "passive"))
    )
    (net (code "122") (name "Net-(PAD28-P)") (class "Default")
      (node (ref "E40") (pin "3") (pinfunction "3_3") (pintype "passive"))
      (node (ref "PAD28") (pin "1") (pinfunction "P_1") (pintype "passive"))
    )
    (net (code "123") (name "Net-(PAD29-P)") (class "Default")
      (node (ref "E40") (pin "4") (pinfunction "4_4") (pintype "passive"))
      (node (ref "PAD29") (pin "1") (pinfunction "P_1") (pintype "passive"))
    )
    (net (code "124") (name "Net-(PAD30-P)") (class "Default")
      (node (ref "E40") (pin "5") (pinfunction "5_5") (pintype "passive"))
      (node (ref "PAD30") (pin "1") (pinfunction "P_1") (pintype "passive"))
    )
    (net (code "125") (name "Net-(PAD31-P)") (class "Default")
      (node (ref "E40") (pin "6") (pinfunction "6_6") (pintype "passive"))
      (node (ref "PAD31") (pin "1") (pinfunction "P_1") (pintype "passive"))
    )
    (net (code "126") (name "Net-(PAD32-P)") (class "Default")
      (node (ref "E40") (pin "7") (pinfunction "7_7") (pintype "passive"))
      (node (ref "PAD32") (pin "1") (pinfunction "P_1") (pintype "passive"))
    )
    (net (code "127") (name "Net-(PAD33-P)") (class "Default")
      (node (ref "E40") (pin "8") (pinfunction "8_8") (pintype "passive"))
      (node (ref "PAD33") (pin "1") (pinfunction "P_1") (pintype "passive"))
    )
    (net (code "128") (name "Net-(PAD34-P)") (class "Default")
      (node (ref "E40") (pin "16") (pinfunction "16_16") (pintype "passive"))
      (node (ref "PAD34") (pin "1") (pinfunction "P_1") (pintype "passive"))
    )
    (net (code "129") (name "Net-(PAD35-P)") (class "Default")
      (node (ref "E40") (pin "15") (pinfunction "15_15") (pintype "passive"))
      (node (ref "PAD35") (pin "1") (pinfunction "P_1") (pintype "passive"))
    )
    (net (code "130") (name "Net-(PAD36-P)") (class "Default")
      (node (ref "E40") (pin "14") (pinfunction "14_14") (pintype "passive"))
      (node (ref "PAD36") (pin "1") (pinfunction "P_1") (pintype "passive"))
    )
    (net (code "131") (name "Net-(PAD37-P)") (class "Default")
      (node (ref "E40") (pin "13") (pinfunction "13_13") (pintype "passive"))
      (node (ref "PAD37") (pin "1") (pinfunction "P_1") (pintype "passive"))
    )
    (net (code "132") (name "Net-(PAD38-P)") (class "Default")
      (node (ref "E40") (pin "12") (pinfunction "12_12") (pintype "passive"))
      (node (ref "PAD38") (pin "1") (pinfunction "P_1") (pintype "passive"))
    )
    (net (code "133") (name "Net-(PAD39-P)") (class "Default")
      (node (ref "E40") (pin "11") (pinfunction "11_11") (pintype "passive"))
      (node (ref "PAD39") (pin "1") (pinfunction "P_1") (pintype "passive"))
    )
    (net (code "134") (name "Net-(PAD40-P)") (class "Default")
      (node (ref "E40") (pin "10") (pinfunction "10_10") (pintype "passive"))
      (node (ref "PAD40") (pin "1") (pinfunction "P_1") (pintype "passive"))
    )
    (net (code "135") (name "Net-(PAD41-P)") (class "Default")
      (node (ref "E40") (pin "9") (pinfunction "9_9") (pintype "passive"))
      (node (ref "PAD41") (pin "1") (pinfunction "P_1") (pintype "passive"))
    )
    (net (code "136") (name "Net-(PAD42-P)") (class "Default")
      (node (ref "E39") (pin "1") (pinfunction "1_1") (pintype "passive"))
      (node (ref "PAD42") (pin "1") (pinfunction "P_1") (pintype "passive"))
    )
    (net (code "137") (name "Net-(PAD43-P)") (class "Default")
      (node (ref "E39") (pin "2") (pinfunction "2_2") (pintype "passive"))
      (node (ref "PAD43") (pin "1") (pinfunction "P_1") (pintype "passive"))
    )
    (net (code "138") (name "Net-(PAD44-P)") (class "Default")
      (node (ref "E39") (pin "3") (pinfunction "3_3") (pintype "passive"))
      (node (ref "PAD44") (pin "1") (pinfunction "P_1") (pintype "passive"))
    )
    (net (code "139") (name "Net-(PAD45-P)") (class "Default")
      (node (ref "E39") (pin "4") (pinfunction "4_4") (pintype "passive"))
      (node (ref "PAD45") (pin "1") (pinfunction "P_1") (pintype "passive"))
    )
    (net (code "140") (name "Net-(PAD46-P)") (class "Default")
      (node (ref "E39") (pin "5") (pinfunction "5_5") (pintype "passive"))
      (node (ref "PAD46") (pin "1") (pinfunction "P_1") (pintype "passive"))
    )
    (net (code "141") (name "Net-(PAD47-P)") (class "Default")
      (node (ref "E39") (pin "6") (pinfunction "6_6") (pintype "passive"))
      (node (ref "PAD47") (pin "1") (pinfunction "P_1") (pintype "passive"))
    )
    (net (code "142") (name "Net-(PAD48-P)") (class "Default")
      (node (ref "E39") (pin "7") (pinfunction "7_7") (pintype "passive"))
      (node (ref "PAD48") (pin "1") (pinfunction "P_1") (pintype "passive"))
    )
    (net (code "143") (name "Net-(PAD49-P)") (class "Default")
      (node (ref "E39") (pin "8") (pinfunction "8_8") (pintype "passive"))
      (node (ref "PAD49") (pin "1") (pinfunction "P_1") (pintype "passive"))
    )
    (net (code "144") (name "Net-(PAD50-P)") (class "Default")
      (node (ref "E39") (pin "16") (pinfunction "16_16") (pintype "passive"))
      (node (ref "PAD50") (pin "1") (pinfunction "P_1") (pintype "passive"))
    )
    (net (code "145") (name "Net-(PAD51-P)") (class "Default")
      (node (ref "E39") (pin "15") (pinfunction "15_15") (pintype "passive"))
      (node (ref "PAD51") (pin "1") (pinfunction "P_1") (pintype "passive"))
    )
    (net (code "146") (name "Net-(PAD52-P)") (class "Default")
      (node (ref "E39") (pin "14") (pinfunction "14_14") (pintype "passive"))
      (node (ref "PAD52") (pin "1") (pinfunction "P_1") (pintype "passive"))
    )
    (net (code "147") (name "Net-(PAD53-P)") (class "Default")
      (node (ref "E39") (pin "13") (pinfunction "13_13") (pintype "passive"))
      (node (ref "PAD53") (pin "1") (pinfunction "P_1") (pintype "passive"))
    )
    (net (code "148") (name "Net-(PAD54-P)") (class "Default")
      (node (ref "E39") (pin "12") (pinfunction "12_12") (pintype "passive"))
      (node (ref "PAD54") (pin "1") (pinfunction "P_1") (pintype "passive"))
    )
    (net (code "149") (name "Net-(PAD55-P)") (class "Default")
      (node (ref "E39") (pin "11") (pinfunction "11_11") (pintype "passive"))
      (node (ref "PAD55") (pin "1") (pinfunction "P_1") (pintype "passive"))
    )
    (net (code "150") (name "Net-(PAD56-P)") (class "Default")
      (node (ref "E39") (pin "10") (pinfunction "10_10") (pintype "passive"))
      (node (ref "PAD56") (pin "1") (pinfunction "P_1") (pintype "passive"))
    )
    (net (code "151") (name "Net-(PAD57-P)") (class "Default")
      (node (ref "E39") (pin "9") (pinfunction "9_9") (pintype "passive"))
      (node (ref "PAD57") (pin "1") (pinfunction "P_1") (pintype "passive"))
    )
    (net (code "152") (name "PARITY") (class "Default")
      (node (ref "E15") (pin "1") (pinfunction "I0_1") (pintype "input"))
      (node (ref "E15") (pin "13") (pinfunction "I1_13") (pintype "input"))
      (node (ref "E15") (pin "2") (pinfunction "I1_2") (pintype "input"))
      (node (ref "E4") (pin "15") (pinfunction "RCO_15") (pintype "output"))
    )
    (net (code "153") (name "RD") (class "Default")
      (node (ref "E25") (pin "1") (pinfunction "I_1") (pintype "input"))
      (node (ref "E32") (pin "10") (pinfunction "I1_10") (pintype "input"))
      (node (ref "E35") (pin "10") (pinfunction "O_10") (pintype "output"))
    )
    (net (code "154") (name "RUN") (class "Default")
      (node (ref "E18") (pin "11") (pinfunction "I0_11") (pintype "input"))
      (node (ref "E30") (pin "9") (pinfunction "Q_9") (pintype "output"))
      (node (ref "IC9") (pin "6") (pinfunction "I0_6") (pintype "input"))
      (node (ref "IC9") (pin "7") (pinfunction "I1_7") (pintype "input"))
    )
    (net (code "155") (name "RX_DATA") (class "Default")
      (node (ref "E22") (pin "2") (pinfunction "J_2") (pintype "input"))
      (node (ref "E22") (pin "3") (pinfunction "K_3") (pintype "input"))
      (node (ref "E35") (pin "1") (pinfunction "O_1") (pintype "output"))
    )
    (net (code "156") (name "SHIFT") (class "Default")
      (node (ref "E32") (pin "3") (pinfunction "I0_3") (pintype "input"))
      (node (ref "E35") (pin "4") (pinfunction "O_4") (pintype "output"))
    )
    (net (code "157") (name "TR_SKIP") (class "Default")
      (node (ref "E18") (pin "1") (pinfunction "O_1") (pintype "output"))
      (node (ref "E20") (pin "1") (pinfunction "I0_1") (pintype "input"))
      (node (ref "E26") (pin "2") (pinfunction "I1_2") (pintype "input"))
    )
    (net (code "158") (name "VCC") (class "Default")
      (node (ref "C1") (pin "1") (pinfunction "1_1") (pintype "passive"))
      (node (ref "C10") (pin "1") (pinfunction "1_1") (pintype "passive"))
      (node (ref "C11") (pin "1") (pinfunction "1_1") (pintype "passive"))
      (node (ref "C12") (pin "1") (pinfunction "1_1") (pintype "passive"))
      (node (ref "C13") (pin "1") (pinfunction "1_1") (pintype "passive"))
      (node (ref "C14") (pin "1") (pinfunction "1_1") (pintype "passive"))
      (node (ref "C15") (pin "1") (pinfunction "1_1") (pintype "passive"))
      (node (ref "C16") (pin "1") (pinfunction "1_1") (pintype "passive"))
      (node (ref "C17") (pin "1") (pinfunction "1_1") (pintype "passive"))
      (node (ref "C18") (pin "1") (pinfunction "1_1") (pintype "passive"))
      (node (ref "C19") (pin "1") (pinfunction "1_1") (pintype "passive"))
      (node (ref "C2") (pin "1") (pinfunction "1_1") (pintype "passive"))
      (node (ref "C20") (pin "1") (pinfunction "1_1") (pintype "passive"))
      (node (ref "C21") (pin "1") (pinfunction "1_1") (pintype "passive"))
      (node (ref "C22") (pin "1") (pinfunction "1_1") (pintype "passive"))
      (node (ref "C23") (pin "1") (pinfunction "1_1") (pintype "passive"))
      (node (ref "C24") (pin "1") (pinfunction "1_1") (pintype "passive"))
      (node (ref "C25") (pin "1") (pinfunction "1_1") (pintype "passive"))
      (node (ref "C26") (pin "1") (pinfunction "1_1") (pintype "passive"))
      (node (ref "C27") (pin "1") (pinfunction "1_1") (pintype "passive"))
      (node (ref "C28") (pin "1") (pinfunction "1_1") (pintype "passive"))
      (node (ref "C29") (pin "1") (pinfunction "1_1") (pintype "passive"))
      (node (ref "C3") (pin "1") (pinfunction "1_1") (pintype "passive"))
      (node (ref "C30") (pin "1") (pinfunction "1_1") (pintype "passive"))
      (node (ref "C31") (pin "1") (pinfunction "1_1") (pintype "passive"))
      (node (ref "C32") (pin "1") (pinfunction "1_1") (pintype "passive"))
      (node (ref "C33") (pin "1") (pinfunction "1_1") (pintype "passive"))
      (node (ref "C34") (pin "1") (pinfunction "1_1") (pintype "passive"))
      (node (ref "C35") (pin "1") (pinfunction "1_1") (pintype "passive"))
      (node (ref "C36") (pin "1") (pinfunction "1_1") (pintype "passive"))
      (node (ref "C37") (pin "1") (pinfunction "1_1") (pintype "passive"))
      (node (ref "C38") (pin "1") (pinfunction "1_1") (pintype "passive"))
      (node (ref "C39") (pin "1") (pinfunction "1_1") (pintype "passive"))
      (node (ref "C4") (pin "1") (pinfunction "1_1") (pintype "passive"))
      (node (ref "C40") (pin "+") (pinfunction "+_+") (pintype "passive"))
      (node (ref "C5") (pin "1") (pinfunction "1_1") (pintype "passive"))
      (node (ref "C6") (pin "1") (pinfunction "1_1") (pintype "passive"))
      (node (ref "C7") (pin "1") (pinfunction "1_1") (pintype "passive"))
      (node (ref "C8") (pin "1") (pinfunction "1_1") (pintype "passive"))
      (node (ref "C9") (pin "1") (pinfunction "1_1") (pintype "passive"))
      (node (ref "E1") (pin "4") (pinfunction "I1_4") (pintype "input"))
      (node (ref "E1") (pin "5") (pinfunction "I2_5") (pintype "input"))
      (node (ref "E14") (pin "6") (pinfunction "G1_6") (pintype "input"))
      (node (ref "E16") (pin "10") (pinfunction "PRE_10") (pintype "input"))
      (node (ref "E16") (pin "4") (pinfunction "PRE_4") (pintype "input"))
      (node (ref "E17") (pin "16") (pinfunction "K_16") (pintype "input"))
      (node (ref "E17") (pin "4") (pinfunction "J_4") (pintype "input"))
      (node (ref "E17") (pin "7") (pinfunction "PRE_7") (pintype "input"))
      (node (ref "E19") (pin "12") (pinfunction "K_12") (pintype "input"))
      (node (ref "E19") (pin "16") (pinfunction "K_16") (pintype "input"))
      (node (ref "E19") (pin "4") (pinfunction "J_4") (pintype "input"))
      (node (ref "E19") (pin "9") (pinfunction "J_9") (pintype "input"))
      (node (ref "E2") (pin "10") (pinfunction "PRE_10") (pintype "input"))
      (node (ref "E2") (pin "11") (pinfunction "CLK_11") (pintype "input"))
      (node (ref "E2") (pin "12") (pinfunction "D_12") (pintype "input"))
      (node (ref "E2") (pin "13") (pinfunction "CLR_13") (pintype "input"))
      (node (ref "E20") (pin "10") (pinfunction "I1_10") (pintype "input"))
      (node (ref "E20") (pin "9") (pinfunction "I0_9") (pintype "input"))
      (node (ref "E25") (pin "11") (pinfunction "I_11") (pintype "input"))
      (node (ref "E25") (pin "13") (pinfunction "I_13") (pintype "input"))
      (node (ref "E30") (pin "10") (pinfunction "PRE_10") (pintype "input"))
      (node (ref "E30") (pin "12") (pinfunction "D_12") (pintype "input"))
      (node (ref "E30") (pin "4") (pinfunction "PRE_4") (pintype "input"))
      (node (ref "R1") (pin "2") (pinfunction "2_2") (pintype "passive"))
      (node (ref "R18") (pin "2") (pinfunction "2_2") (pintype "passive"))
      (node (ref "R19") (pin "1") (pinfunction "1_1") (pintype "passive"))
      (node (ref "R2") (pin "2") (pinfunction "2_2") (pintype "passive"))
      (node (ref "R20") (pin "2") (pinfunction "2_2") (pintype "passive"))
      (node (ref "R3") (pin "2") (pinfunction "2_2") (pintype "passive"))
      (node (ref "R4") (pin "2") (pinfunction "2_2") (pintype "passive"))
      (node (ref "R5") (pin "2") (pinfunction "2_2") (pintype "passive"))
      (node (ref "R6") (pin "2") (pinfunction "2_2") (pintype "passive"))
      (node (ref "R7") (pin "2") (pinfunction "2_2") (pintype "passive"))
      (node (ref "R8") (pin "2") (pinfunction "2_2") (pintype "passive"))
      (node (ref "R9") (pin "2") (pinfunction "2_2") (pintype "passive"))
      (node (ref "SL1") (pin "1") (pinfunction "S_1") (pintype "passive"))
    )
    (net (code "159") (name "WRT") (class "Default")
      (node (ref "E10") (pin "5") (pinfunction "I2_5") (pintype "input"))
      (node (ref "E15") (pin "10") (pinfunction "I1_10") (pintype "input"))
      (node (ref "E25") (pin "2") (pinfunction "O_2") (pintype "output"))
      (node (ref "IC7") (pin "6") (pinfunction "I0_6") (pintype "input"))
    )
    (net (code "160") (name "XDR2") (class "Default")
      (node (ref "E10") (pin "2") (pinfunction "I1_2") (pintype "input"))
      (node (ref "E5") (pin "12") (pinfunction "I0_12") (pintype "input"))
      (node (ref "E5") (pin "8") (pinfunction "O_8") (pintype "output"))
    )
    (net (code "161") (name "XFER_REQ") (class "Default")
      (node (ref "E20") (pin "12") (pinfunction "I0_12") (pintype "input"))
      (node (ref "E26") (pin "1") (pinfunction "I0_1") (pintype "input"))
      (node (ref "E36") (pin "4") (pinfunction "O_4") (pintype "output"))
    )
    (net (code "162") (name "unconnected-(D34L1-2-PadB)") (class "Default")
      (node (ref "D34L1") (pin "B") (pinfunction "2_B") (pintype "bidirectional"))
    )
    (net (code "163") (name "unconnected-(D34L1-34-PadNN)") (class "Default")
      (node (ref "D34L1") (pin "NN") (pinfunction "34_NN") (pintype "bidirectional"))
    )
    (net (code "164") (name "unconnected-(D34L1-38-PadTT)") (class "Default")
      (node (ref "D34L1") (pin "TT") (pinfunction "38_TT") (pintype "bidirectional"))
    )
    (net (code "165") (name "unconnected-(D34L1-40-PadVV)") (class "Default")
      (node (ref "D34L1") (pin "VV") (pinfunction "40_VV") (pintype "bidirectional"))
    )
    (net (code "166") (name "unconnected-(D34L2-2-PadB)") (class "Default")
      (node (ref "D34L2") (pin "B") (pinfunction "2_B") (pintype "bidirectional"))
    )
    (net (code "167") (name "unconnected-(D34L2-34-PadNN)") (class "Default")
      (node (ref "D34L2") (pin "NN") (pinfunction "34_NN") (pintype "bidirectional"))
    )
    (net (code "168") (name "unconnected-(D34L2-38-PadTT)") (class "Default")
      (node (ref "D34L2") (pin "TT") (pinfunction "38_TT") (pintype "bidirectional"))
    )
    (net (code "169") (name "unconnected-(D34L2-40-PadVV)") (class "Default")
      (node (ref "D34L2") (pin "VV") (pinfunction "40_VV") (pintype "bidirectional"))
    )
    (net (code "170") (name "unconnected-(D35L1-2-PadB)") (class "Default")
      (node (ref "D35L1") (pin "B") (pinfunction "2_B") (pintype "bidirectional"))
    )
    (net (code "171") (name "unconnected-(D35L1-40-PadVV)") (class "Default")
      (node (ref "D35L1") (pin "VV") (pinfunction "40_VV") (pintype "bidirectional"))
    )
    (net (code "172") (name "unconnected-(D35L2-2-PadB)") (class "Default")
      (node (ref "D35L2") (pin "B") (pinfunction "2_B") (pintype "bidirectional"))
    )
    (net (code "173") (name "unconnected-(D35L2-40-PadVV)") (class "Default")
      (node (ref "D35L2") (pin "VV") (pinfunction "40_VV") (pintype "bidirectional"))
    )
    (net (code "174") (name "unconnected-(D36L1-2-PadB)") (class "Default")
      (node (ref "D36L1") (pin "B") (pinfunction "2_B") (pintype "bidirectional"))
    )
    (net (code "175") (name "unconnected-(D36L1-40-PadVV)") (class "Default")
      (node (ref "D36L1") (pin "VV") (pinfunction "40_VV") (pintype "bidirectional"))
    )
    (net (code "176") (name "unconnected-(D36L2-2-PadB)") (class "Default")
      (node (ref "D36L2") (pin "B") (pinfunction "2_B") (pintype "bidirectional"))
    )
    (net (code "177") (name "unconnected-(D36L2-40-PadVV)") (class "Default")
      (node (ref "D36L2") (pin "VV") (pinfunction "40_VV") (pintype "bidirectional"))
    )
    (net (code "178") (name "unconnected-(E2A-Q-Pad5)") (class "Default")
      (node (ref "E2") (pin "5") (pinfunction "Q_5") (pintype "output"))
    )
    (net (code "179") (name "unconnected-(E2B-Q-Pad9)") (class "Default")
      (node (ref "E2") (pin "9") (pinfunction "Q_9") (pintype "output"))
    )
    (net (code "180") (name "unconnected-(E2B-~{Q}-Pad8)") (class "Default")
      (node (ref "E2") (pin "8") (pinfunction "~{Q}_8") (pintype "output"))
    )
    (net (code "181") (name "unconnected-(E4A-QA-Pad14)") (class "Default")
      (node (ref "E4") (pin "14") (pinfunction "QA_14") (pintype "output"))
    )
    (net (code "182") (name "unconnected-(E4A-QB-Pad13)") (class "Default")
      (node (ref "E4") (pin "13") (pinfunction "QB_13") (pintype "output"))
    )
    (net (code "183") (name "unconnected-(E4A-QC-Pad12)") (class "Default")
      (node (ref "E4") (pin "12") (pinfunction "QC_12") (pintype "output"))
    )
    (net (code "184") (name "unconnected-(E4A-QD-Pad11)") (class "Default")
      (node (ref "E4") (pin "11") (pinfunction "QD_11") (pintype "output"))
    )
    (net (code "185") (name "unconnected-(E11A-Y0-Pad15)") (class "Default")
      (node (ref "E11") (pin "15") (pinfunction "Y0_15") (pintype "output"))
    )
    (net (code "186") (name "unconnected-(E11A-Y2-Pad13)") (class "Default")
      (node (ref "E11") (pin "13") (pinfunction "Y2_13") (pintype "output"))
    )
    (net (code "187") (name "unconnected-(E11A-Y3-Pad12)") (class "Default")
      (node (ref "E11") (pin "12") (pinfunction "Y3_12") (pintype "output"))
    )
    (net (code "188") (name "unconnected-(E11A-Y4-Pad11)") (class "Default")
      (node (ref "E11") (pin "11") (pinfunction "Y4_11") (pintype "output"))
    )
    (net (code "189") (name "unconnected-(E11A-Y5-Pad10)") (class "Default")
      (node (ref "E11") (pin "10") (pinfunction "Y5_10") (pintype "output"))
    )
    (net (code "190") (name "unconnected-(E11A-Y6-Pad9)") (class "Default")
      (node (ref "E11") (pin "9") (pinfunction "Y6_9") (pintype "output"))
    )
    (net (code "191") (name "unconnected-(E12A-Y0-Pad15)") (class "Default")
      (node (ref "E12") (pin "15") (pinfunction "Y0_15") (pintype "output"))
    )
    (net (code "192") (name "unconnected-(E12A-Y1-Pad14)") (class "Default")
      (node (ref "E12") (pin "14") (pinfunction "Y1_14") (pintype "output"))
    )
    (net (code "193") (name "unconnected-(E12A-Y4-Pad11)") (class "Default")
      (node (ref "E12") (pin "11") (pinfunction "Y4_11") (pintype "output"))
    )
    (net (code "194") (name "unconnected-(E12A-Y5-Pad10)") (class "Default")
      (node (ref "E12") (pin "10") (pinfunction "Y5_10") (pintype "output"))
    )
    (net (code "195") (name "unconnected-(E12A-Y6-Pad9)") (class "Default")
      (node (ref "E12") (pin "9") (pinfunction "Y6_9") (pintype "output"))
    )
    (net (code "196") (name "unconnected-(E12A-Y7-Pad7)") (class "Default")
      (node (ref "E12") (pin "7") (pinfunction "Y7_7") (pintype "output"))
    )
    (net (code "197") (name "unconnected-(E13A-Y0-Pad15)") (class "Default")
      (node (ref "E13") (pin "15") (pinfunction "Y0_15") (pintype "output"))
    )
    (net (code "198") (name "unconnected-(E13A-Y1-Pad14)") (class "Default")
      (node (ref "E13") (pin "14") (pinfunction "Y1_14") (pintype "output"))
    )
    (net (code "199") (name "unconnected-(E13A-Y2-Pad13)") (class "Default")
      (node (ref "E13") (pin "13") (pinfunction "Y2_13") (pintype "output"))
    )
    (net (code "200") (name "unconnected-(E13A-Y3-Pad12)") (class "Default")
      (node (ref "E13") (pin "12") (pinfunction "Y3_12") (pintype "output"))
    )
    (net (code "201") (name "unconnected-(E17B-Q-Pad11)") (class "Default")
      (node (ref "E17") (pin "11") (pinfunction "Q_11") (pintype "output"))
    )
    (net (code "202") (name "unconnected-(E19A-Q-Pad15)") (class "Default")
      (node (ref "E19") (pin "15") (pinfunction "Q_15") (pintype "output"))
    )
    (net (code "203") (name "unconnected-(E19B-Q-Pad11)") (class "Default")
      (node (ref "E19") (pin "11") (pinfunction "Q_11") (pintype "output"))
    )
    (net (code "204") (name "unconnected-(E20C-O-Pad8)") (class "Default")
      (node (ref "E20") (pin "8") (pinfunction "O_8") (pintype "output"))
    )
    (net (code "205") (name "unconnected-(E21A-~{QD}-Pad11)") (class "Default")
      (node (ref "E21") (pin "11") (pinfunction "~{QD}_11") (pintype "output"))
    )
    (net (code "206") (name "unconnected-(E22A-~{QD}-Pad11)") (class "Default")
      (node (ref "E22") (pin "11") (pinfunction "~{QD}_11") (pintype "output"))
    )
    (net (code "207") (name "unconnected-(E23A-~{QD}-Pad11)") (class "Default")
      (node (ref "E23") (pin "11") (pinfunction "~{QD}_11") (pintype "output"))
    )
    (net (code "208") (name "unconnected-(E26D-O-Pad11)") (class "Default")
      (node (ref "E26") (pin "11") (pinfunction "O_11") (pintype "output"))
    )
    (net (code "209") (name "unconnected-(E30A-~{Q}-Pad6)") (class "Default")
      (node (ref "E30") (pin "6") (pinfunction "~{Q}_6") (pintype "output"))
    )
    (net (code "210") (name "unconnected-(E30B-~{Q}-Pad8)") (class "Default")
      (node (ref "E30") (pin "8") (pinfunction "~{Q}_8") (pintype "output"))
    )
    (net (code "211") (name "unconnected-(E36D-O-Pad13)") (class "Default")
      (node (ref "E36") (pin "13") (pinfunction "O_13") (pintype "output"))
    )
    (net (code "212") (name "unconnected-(LASTDEV-Pad8)") (class "Default")
      (node (ref "LASTDEV") (pin "8") (pinfunction "8_8") (pintype "passive"))
    )
    (net (code "213") (name "unconnected-(LASTDEV-Pad9)") (class "Default")
      (node (ref "LASTDEV") (pin "9") (pinfunction "9_9") (pintype "passive"))
    )
    (net (code "214") (name "unconnected-(LASTDEV-Pad10)") (class "Default")
      (node (ref "LASTDEV") (pin "10") (pinfunction "10_10") (pintype "passive"))
    )
    (net (code "215") (name "~{ACB00}") (class "Default")
      (node (ref "D34L1") (pin "D") (pinfunction "4_D") (pintype "bidirectional"))
      (node (ref "D34L2") (pin "D") (pinfunction "4_D") (pintype "bidirectional"))
      (node (ref "IC6") (pin "3") (pinfunction "O_3") (pintype "open_collector"))
    )
    (net (code "216") (name "~{ACB01}") (class "Default")
      (node (ref "D34L1") (pin "J") (pinfunction "8_J") (pintype "bidirectional"))
      (node (ref "D34L2") (pin "J") (pinfunction "8_J") (pintype "bidirectional"))
      (node (ref "IC6") (pin "5") (pinfunction "O_5") (pintype "open_collector"))
    )
    (net (code "217") (name "~{ACB02}") (class "Default")
      (node (ref "D34L1") (pin "N") (pinfunction "12_N") (pintype "bidirectional"))
      (node (ref "D34L2") (pin "N") (pinfunction "12_N") (pintype "bidirectional"))
      (node (ref "IC1") (pin "3") (pinfunction "O_3") (pintype "open_collector"))
    )
    (net (code "218") (name "~{ACB03}") (class "Default")
      (node (ref "D34L1") (pin "T") (pinfunction "16_T") (pintype "bidirectional"))
      (node (ref "D34L2") (pin "T") (pinfunction "16_T") (pintype "bidirectional"))
      (node (ref "IC2") (pin "5") (pinfunction "O_5") (pintype "open_collector"))
    )
    (net (code "219") (name "~{ACB04}") (class "Default")
      (node (ref "D34L1") (pin "X") (pinfunction "20_X") (pintype "bidirectional"))
      (node (ref "D34L2") (pin "X") (pinfunction "20_X") (pintype "bidirectional"))
      (node (ref "IC1") (pin "5") (pinfunction "O_5") (pintype "open_collector"))
    )
    (net (code "220") (name "~{ACB05}") (class "Default")
      (node (ref "D34L1") (pin "BB") (pinfunction "24_BB") (pintype "bidirectional"))
      (node (ref "D34L2") (pin "BB") (pinfunction "24_BB") (pintype "bidirectional"))
      (node (ref "IC4") (pin "3") (pinfunction "O_3") (pintype "open_collector"))
    )
    (net (code "221") (name "~{ACB06}") (class "Default")
      (node (ref "D34L1") (pin "FF") (pinfunction "28_FF") (pintype "bidirectional"))
      (node (ref "D34L2") (pin "FF") (pinfunction "28_FF") (pintype "bidirectional"))
      (node (ref "IC3") (pin "3") (pinfunction "O_3") (pintype "open_collector"))
    )
    (net (code "222") (name "~{ACB07}") (class "Default")
      (node (ref "D34L1") (pin "LL") (pinfunction "32_LL") (pintype "bidirectional"))
      (node (ref "D34L2") (pin "LL") (pinfunction "32_LL") (pintype "bidirectional"))
      (node (ref "IC3") (pin "5") (pinfunction "O_5") (pintype "open_collector"))
    )
    (net (code "223") (name "~{ACB08}") (class "Default")
      (node (ref "D34L1") (pin "RR") (pinfunction "36_RR") (pintype "bidirectional"))
      (node (ref "D34L2") (pin "RR") (pinfunction "36_RR") (pintype "bidirectional"))
      (node (ref "IC4") (pin "5") (pinfunction "O_5") (pintype "open_collector"))
    )
    (net (code "224") (name "~{ACB09}") (class "Default")
      (node (ref "D34L1") (pin "F") (pinfunction "6_F") (pintype "bidirectional"))
      (node (ref "D34L2") (pin "F") (pinfunction "6_F") (pintype "bidirectional"))
      (node (ref "IC5") (pin "3") (pinfunction "O_3") (pintype "open_collector"))
    )
    (net (code "225") (name "~{ACB10}") (class "Default")
      (node (ref "D34L1") (pin "L") (pinfunction "10_L") (pintype "bidirectional"))
      (node (ref "D34L2") (pin "L") (pinfunction "10_L") (pintype "bidirectional"))
      (node (ref "IC5") (pin "5") (pinfunction "O_5") (pintype "open_collector"))
    )
    (net (code "226") (name "~{ACB11}") (class "Default")
      (node (ref "D34L1") (pin "R") (pinfunction "14_R") (pintype "bidirectional"))
      (node (ref "D34L2") (pin "R") (pinfunction "14_R") (pintype "bidirectional"))
      (node (ref "IC2") (pin "3") (pinfunction "O_3") (pintype "open_collector"))
    )
    (net (code "227") (name "~{ACCLEAR}") (class "Default")
      (node (ref "D34L1") (pin "DD") (pinfunction "26_DD") (pintype "bidirectional"))
      (node (ref "D34L2") (pin "DD") (pinfunction "26_DD") (pintype "bidirectional"))
      (node (ref "IC7") (pin "3") (pinfunction "O_3") (pintype "open_collector"))
    )
    (net (code "228") (name "~{BMB03}") (class "Default")
      (node (ref "D35L1") (pin "T") (pinfunction "16_T") (pintype "bidirectional"))
      (node (ref "D35L2") (pin "T") (pinfunction "16_T") (pintype "bidirectional"))
    )
    (net (code "229") (name "~{BMB04}") (class "Default")
      (node (ref "D35L1") (pin "BB") (pinfunction "24_BB") (pintype "bidirectional"))
      (node (ref "D35L2") (pin "BB") (pinfunction "24_BB") (pintype "bidirectional"))
    )
    (net (code "230") (name "~{BMB05}") (class "Default")
      (node (ref "D35L1") (pin "LL") (pinfunction "32_LL") (pintype "bidirectional"))
      (node (ref "D35L2") (pin "LL") (pinfunction "32_LL") (pintype "bidirectional"))
    )
    (net (code "231") (name "~{BMB06}") (class "Default")
      (node (ref "D35L1") (pin "F") (pinfunction "6_F") (pintype "bidirectional"))
      (node (ref "D35L2") (pin "F") (pinfunction "6_F") (pintype "bidirectional"))
    )
    (net (code "232") (name "~{BMB07}") (class "Default")
      (node (ref "D35L1") (pin "R") (pinfunction "14_R") (pintype "bidirectional"))
      (node (ref "D35L2") (pin "R") (pinfunction "14_R") (pintype "bidirectional"))
    )
    (net (code "233") (name "~{BMB08}") (class "Default")
      (node (ref "D35L1") (pin "Z") (pinfunction "22_Z") (pintype "bidirectional"))
      (node (ref "D35L2") (pin "Z") (pinfunction "22_Z") (pintype "bidirectional"))
    )
    (net (code "234") (name "~{BRUN}") (class "Default")
      (node (ref "D34L1") (pin "JJ") (pinfunction "30_JJ") (pintype "bidirectional"))
      (node (ref "D34L2") (pin "JJ") (pinfunction "30_JJ") (pintype "bidirectional"))
    )
    (net (code "235") (name "~{CLK_PARITY}") (class "Default")
      (node (ref "E17") (pin "6") (pinfunction "CLK_6") (pintype "input"))
      (node (ref "E32") (pin "6") (pinfunction "O_6") (pintype "output"))
      (node (ref "E5") (pin "4") (pinfunction "I0_4") (pintype "input"))
      (node (ref "E5") (pin "5") (pinfunction "I1_5") (pintype "input"))
    )
    (net (code "236") (name "~{DONE}") (class "Default")
      (node (ref "E10") (pin "4") (pinfunction "I1_4") (pintype "input"))
      (node (ref "E25") (pin "4") (pinfunction "O_4") (pintype "output"))
      (node (ref "E31") (pin "12") (pinfunction "I2_12") (pintype "input"))
    )
    (net (code "237") (name "~{ENB_BUF_LD}") (class "Default")
      (node (ref "E21") (pin "9") (pinfunction "S/~{L}_9") (pintype "input"))
      (node (ref "E22") (pin "9") (pinfunction "S/~{L}_9") (pintype "input"))
      (node (ref "E23") (pin "9") (pinfunction "S/~{L}_9") (pintype "input"))
      (node (ref "E24") (pin "11") (pinfunction "O_11") (pintype "output"))
      (node (ref "E32") (pin "13") (pinfunction "I2_13") (pintype "input"))
      (node (ref "E32") (pin "2") (pinfunction "I1_2") (pintype "input"))
      (node (ref "E4") (pin "9") (pinfunction "LD_9") (pintype "input"))
    )
    (net (code "238") (name "~{INIT1}") (class "Default")
      (node (ref "E11") (pin "7") (pinfunction "Y7_7") (pintype "output"))
      (node (ref "E2") (pin "4") (pinfunction "PRE_4") (pintype "input"))
    )
    (net (code "239") (name "~{INIT4}") (class "Default")
      (node (ref "E13") (pin "7") (pinfunction "Y7_7") (pintype "output"))
      (node (ref "E2") (pin "3") (pinfunction "CLK_3") (pintype "input"))
    )
    (net (code "240") (name "~{INIT}") (class "Default")
      (node (ref "E15") (pin "6") (pinfunction "O_6") (pintype "output"))
      (node (ref "E16") (pin "1") (pinfunction "CLR_1") (pintype "input"))
      (node (ref "E16") (pin "13") (pinfunction "CLR_13") (pintype "input"))
      (node (ref "E17") (pin "3") (pinfunction "CLR_3") (pintype "input"))
      (node (ref "E19") (pin "3") (pinfunction "CLR_3") (pintype "input"))
      (node (ref "E19") (pin "8") (pinfunction "CLR_8") (pintype "input"))
      (node (ref "E21") (pin "1") (pinfunction "CLR_1") (pintype "input"))
      (node (ref "E22") (pin "1") (pinfunction "CLR_1") (pintype "input"))
      (node (ref "E23") (pin "1") (pinfunction "CLR_1") (pintype "input"))
      (node (ref "E24") (pin "9") (pinfunction "I0_9") (pintype "input"))
      (node (ref "E30") (pin "1") (pinfunction "CLR_1") (pintype "input"))
      (node (ref "E4") (pin "1") (pinfunction "CLR_1") (pintype "input"))
    )
    (net (code "241") (name "~{INTR4}") (class "Default")
      (node (ref "E13") (pin "9") (pinfunction "Y6_9") (pintype "output"))
      (node (ref "E30") (pin "3") (pinfunction "CLK_3") (pintype "input"))
    )
    (net (code "242") (name "~{INT_RQ}") (class "Default")
      (node (ref "D34L1") (pin "Z") (pinfunction "22_Z") (pintype "bidirectional"))
      (node (ref "D34L2") (pin "Z") (pinfunction "22_Z") (pintype "bidirectional"))
      (node (ref "IC10") (pin "5") (pinfunction "O_5") (pintype "open_collector"))
    )
    (net (code "243") (name "~{IOS}") (class "Default")
      (node (ref "D34L1") (pin "V") (pinfunction "18_V") (pintype "bidirectional"))
      (node (ref "D34L2") (pin "V") (pinfunction "18_V") (pintype "bidirectional"))
      (node (ref "IC10") (pin "3") (pinfunction "O_3") (pintype "open_collector"))
    )
    (net (code "244") (name "~{LCD1}") (class "Default")
      (node (ref "E10") (pin "9") (pinfunction "I0_9") (pintype "input"))
      (node (ref "E11") (pin "14") (pinfunction "Y1_14") (pintype "output"))
      (node (ref "E16") (pin "11") (pinfunction "CLK_11") (pintype "input"))
      (node (ref "E16") (pin "3") (pinfunction "CLK_3") (pintype "input"))
      (node (ref "E24") (pin "5") (pinfunction "I1_5") (pintype "input"))
      (node (ref "E25") (pin "5") (pinfunction "I_5") (pintype "input"))
    )
    (net (code "245") (name "~{MAINT}") (class "Default")
      (node (ref "E10") (pin "3") (pinfunction "I0_3") (pintype "input"))
      (node (ref "E16") (pin "8") (pinfunction "~{Q}_8") (pintype "output"))
      (node (ref "E17") (pin "2") (pinfunction "PRE_2") (pintype "input"))
      (node (ref "E19") (pin "2") (pinfunction "PRE_2") (pintype "input"))
      (node (ref "E19") (pin "7") (pinfunction "PRE_7") (pintype "input"))
      (node (ref "E24") (pin "13") (pinfunction "I1_13") (pintype "input"))
      (node (ref "E31") (pin "10") (pinfunction "I1_10") (pintype "input"))
      (node (ref "E31") (pin "5") (pinfunction "I3_5") (pintype "input"))
      (node (ref "E31") (pin "9") (pinfunction "I0_9") (pintype "input"))
    )
    (net (code "246") (name "~{MYDEV}") (class "Default")
      (node (ref "E11") (pin "4") (pinfunction "G2A_4") (pintype "input"))
      (node (ref "E12") (pin "4") (pinfunction "G2A_4") (pintype "input"))
      (node (ref "E13") (pin "4") (pinfunction "G2A_4") (pintype "input"))
      (node (ref "IOT") (pin "1") (pinfunction "P_1") (pintype "passive"))
    )
    (net (code "247") (name "~{PARITY}") (class "Default")
      (node (ref "E15") (pin "12") (pinfunction "I0_12") (pintype "input"))
      (node (ref "E17") (pin "10") (pinfunction "~{Q}_10") (pintype "output"))
    )
    (net (code "248") (name "~{RX_12_BIT}") (class "Default")
      (node (ref "DRIVE") (pin "FF") (pinfunction "28_FF") (pintype "bidirectional"))
      (node (ref "IC8") (pin "3") (pinfunction "O_3") (pintype "open_collector"))
      (node (ref "R16") (pin "2") (pinfunction "2_2") (pintype "passive"))
      (node (ref "R7") (pin "1") (pinfunction "1_1") (pintype "passive"))
    )
    (net (code "249") (name "~{RX_DATA}") (class "Default")
      (node (ref "DRIVE") (pin "BB") (pinfunction "24_BB") (pintype "bidirectional"))
      (node (ref "E35") (pin "2") (pinfunction "I0_2") (pintype "input"))
      (node (ref "IC7") (pin "5") (pinfunction "O_5") (pintype "open_collector"))
      (node (ref "R17") (pin "2") (pinfunction "2_2") (pintype "passive"))
      (node (ref "R8") (pin "1") (pinfunction "1_1") (pintype "passive"))
    )
    (net (code "250") (name "~{RX_DONE}") (class "Default")
      (node (ref "DRIVE") (pin "X") (pinfunction "20_X") (pintype "bidirectional"))
      (node (ref "E36") (pin "8") (pinfunction "I0_8") (pintype "input"))
      (node (ref "R13") (pin "2") (pinfunction "2_2") (pintype "passive"))
      (node (ref "R4") (pin "1") (pinfunction "1_1") (pintype "passive"))
    )
    (net (code "251") (name "~{RX_ERROR}") (class "Default")
      (node (ref "DRIVE") (pin "J") (pinfunction "8_J") (pintype "bidirectional"))
      (node (ref "E36") (pin "3") (pinfunction "I1_3") (pintype "input"))
      (node (ref "R14") (pin "2") (pinfunction "2_2") (pintype "passive"))
      (node (ref "R5") (pin "1") (pinfunction "1_1") (pintype "passive"))
    )
    (net (code "252") (name "~{RX_INIT}") (class "Default")
      (node (ref "DRIVE") (pin "N") (pinfunction "12_N") (pintype "bidirectional"))
      (node (ref "IC8") (pin "5") (pinfunction "O_5") (pintype "open_collector"))
      (node (ref "R20") (pin "1") (pinfunction "1_1") (pintype "passive"))
      (node (ref "R9") (pin "1") (pinfunction "1_1") (pintype "passive"))
    )
    (net (code "253") (name "~{RX_OUT}") (class "Default")
      (node (ref "DRIVE") (pin "RR") (pinfunction "36_RR") (pintype "bidirectional"))
      (node (ref "E35") (pin "8") (pinfunction "I0_8") (pintype "input"))
      (node (ref "R12") (pin "2") (pinfunction "2_2") (pintype "passive"))
      (node (ref "R3") (pin "1") (pinfunction "1_1") (pintype "passive"))
    )
    (net (code "254") (name "~{RX_RUN}") (class "Default")
      (node (ref "DRIVE") (pin "D") (pinfunction "4_D") (pintype "bidirectional"))
      (node (ref "IC9") (pin "5") (pinfunction "O_5") (pintype "open_collector"))
      (node (ref "R15") (pin "2") (pinfunction "2_2") (pintype "passive"))
      (node (ref "R6") (pin "1") (pinfunction "1_1") (pintype "passive"))
    )
    (net (code "255") (name "~{RX_SHIFT}") (class "Default")
      (node (ref "DRIVE") (pin "LL") (pinfunction "32_LL") (pintype "bidirectional"))
      (node (ref "E35") (pin "5") (pinfunction "I0_5") (pintype "input"))
      (node (ref "R10") (pin "2") (pinfunction "2_2") (pintype "passive"))
      (node (ref "R2") (pin "1") (pinfunction "1_1") (pintype "passive"))
    )
    (net (code "256") (name "~{RX_TR_REQ}") (class "Default")
      (node (ref "DRIVE") (pin "T") (pinfunction "16_T") (pintype "bidirectional"))
      (node (ref "E36") (pin "5") (pinfunction "I0_5") (pintype "input"))
      (node (ref "R1") (pin "1") (pinfunction "1_1") (pintype "passive"))
      (node (ref "R11") (pin "2") (pinfunction "2_2") (pintype "passive"))
    )
    (net (code "257") (name "~{SDN4}") (class "Default")
      (node (ref "E13") (pin "10") (pinfunction "Y5_10") (pintype "output"))
      (node (ref "E18") (pin "8") (pinfunction "I0_8") (pintype "input"))
    )
    (net (code "258") (name "~{SER4}") (class "Default")
      (node (ref "E13") (pin "11") (pinfunction "Y4_11") (pintype "output"))
      (node (ref "E18") (pin "5") (pinfunction "I0_5") (pintype "input"))
    )
    (net (code "259") (name "~{STR2}") (class "Default")
      (node (ref "E12") (pin "12") (pinfunction "Y3_12") (pintype "output"))
      (node (ref "E18") (pin "2") (pinfunction "I0_2") (pintype "input"))
    )
    (net (code "260") (name "~{XDR2}") (class "Default")
      (node (ref "E12") (pin "13") (pinfunction "Y2_13") (pintype "output"))
      (node (ref "E24") (pin "4") (pinfunction "I0_4") (pintype "input"))
      (node (ref "E25") (pin "9") (pinfunction "I_9") (pintype "input"))
      (node (ref "E35") (pin "12") (pinfunction "I1_12") (pintype "input"))
      (node (ref "E5") (pin "10") (pinfunction "I1_10") (pintype "input"))
      (node (ref "E5") (pin "9") (pinfunction "I0_9") (pintype "input"))
    )
  )
)
